# MAAV_Vehicle_13v1.net
KiCad netlist of a schematic drawn in EAGLE
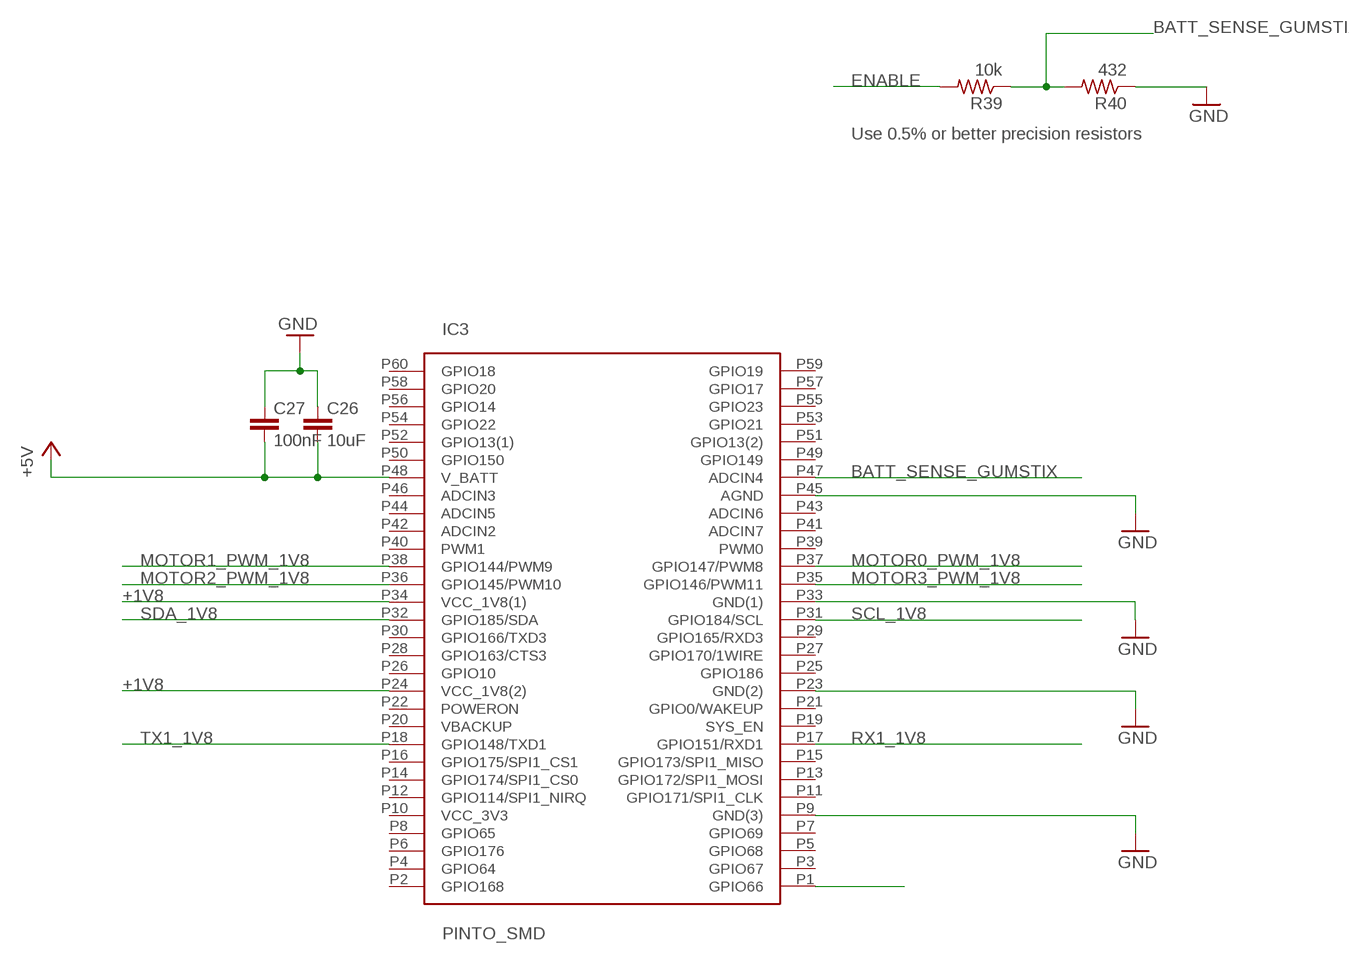
[diagram p0: schematic, sheet 1]
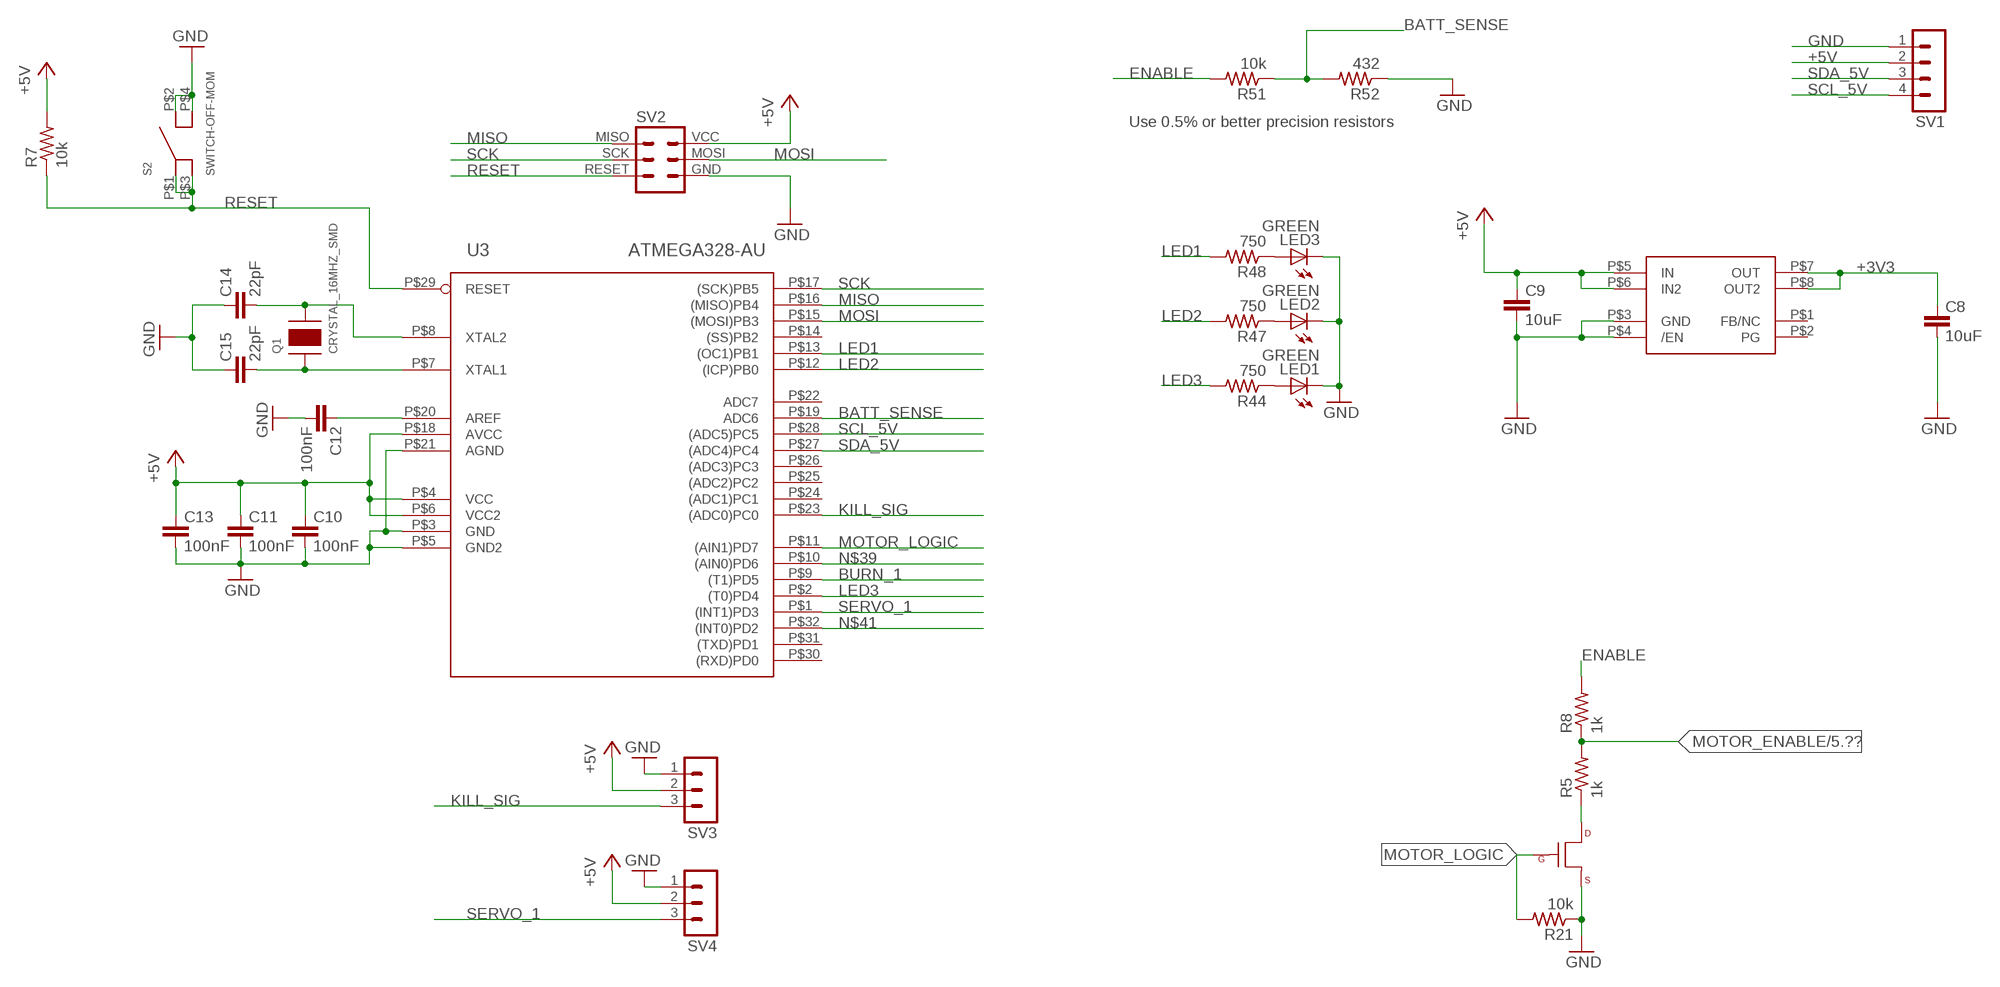
[diagram p1: schematic, sheet 2]
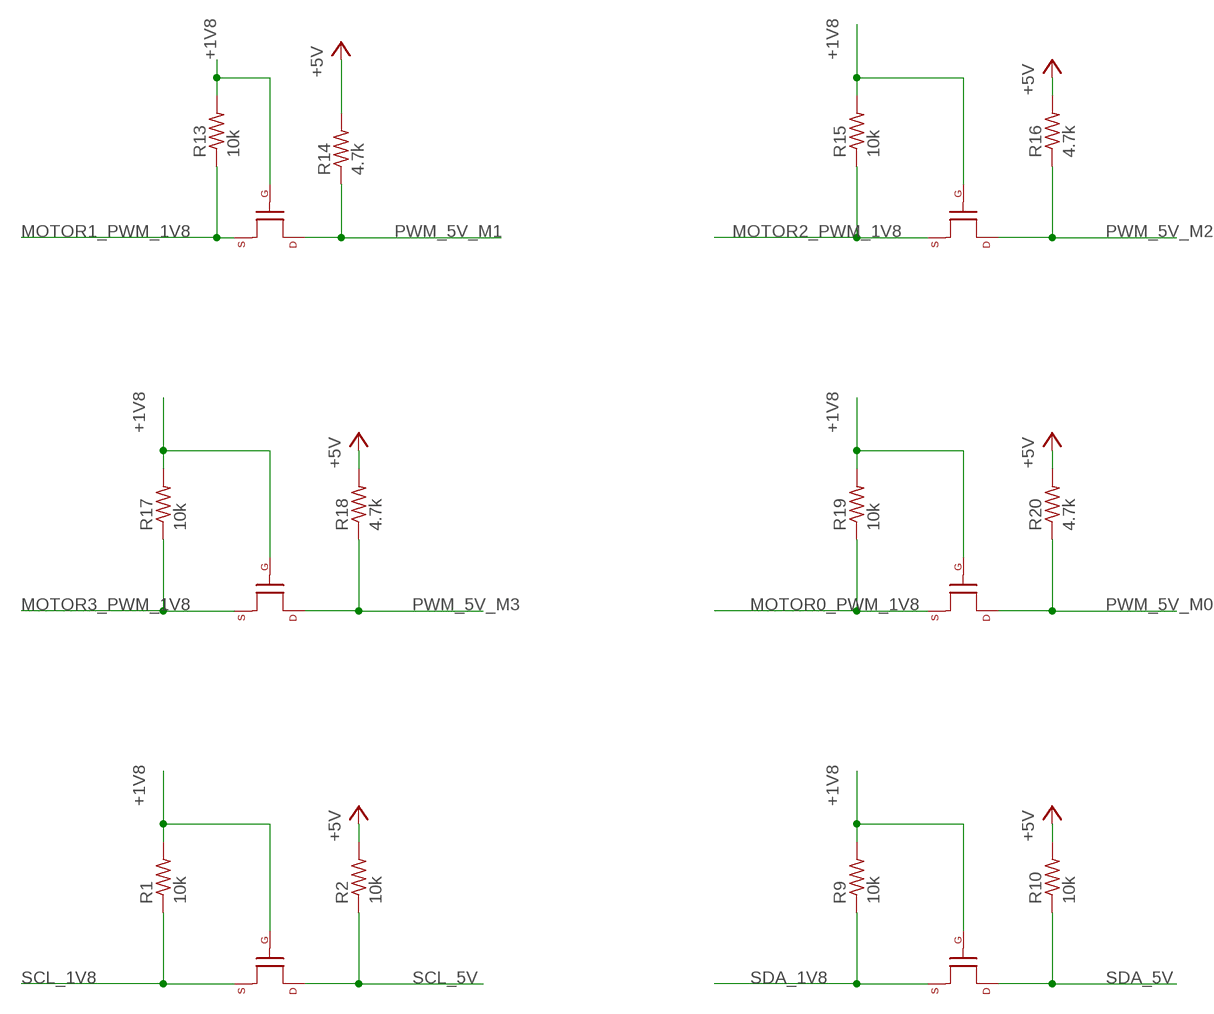
[diagram p2: schematic, sheet 3]
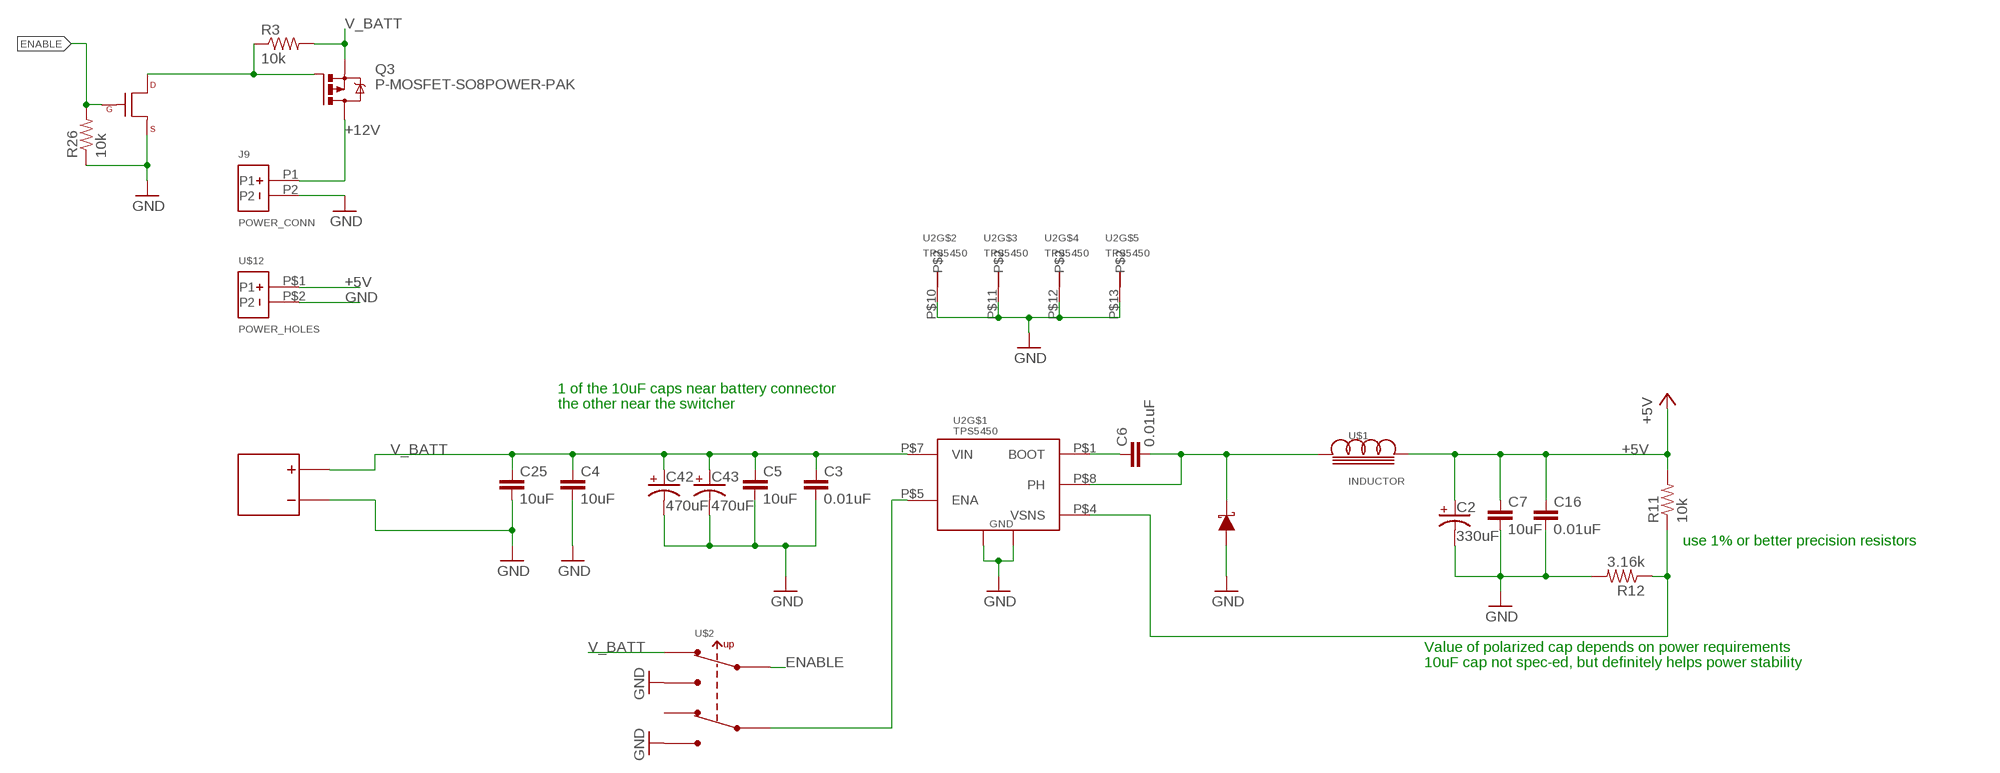
[diagram p3: schematic, sheet 4]
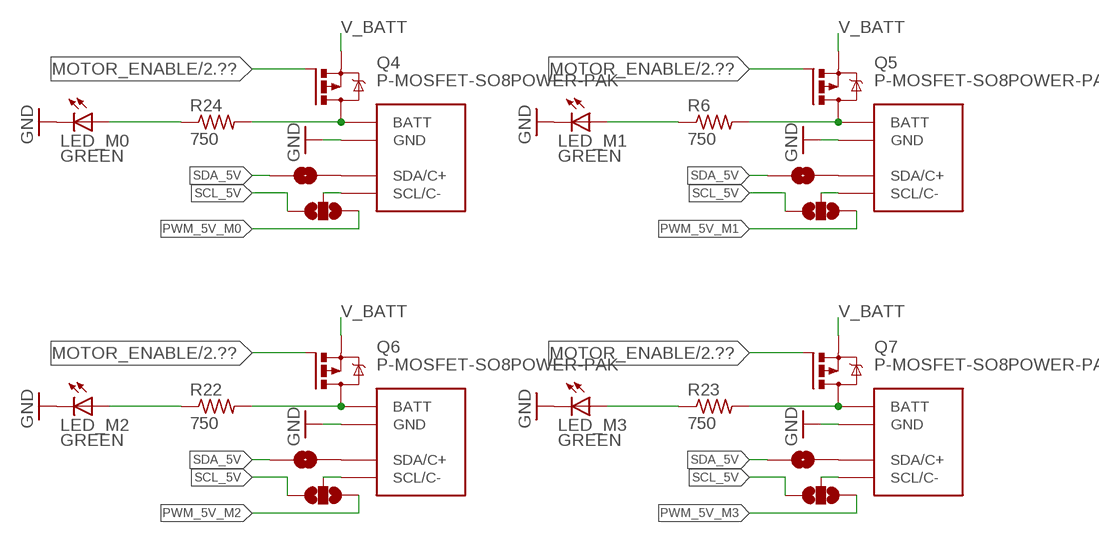
[diagram p4: schematic, sheet 5]
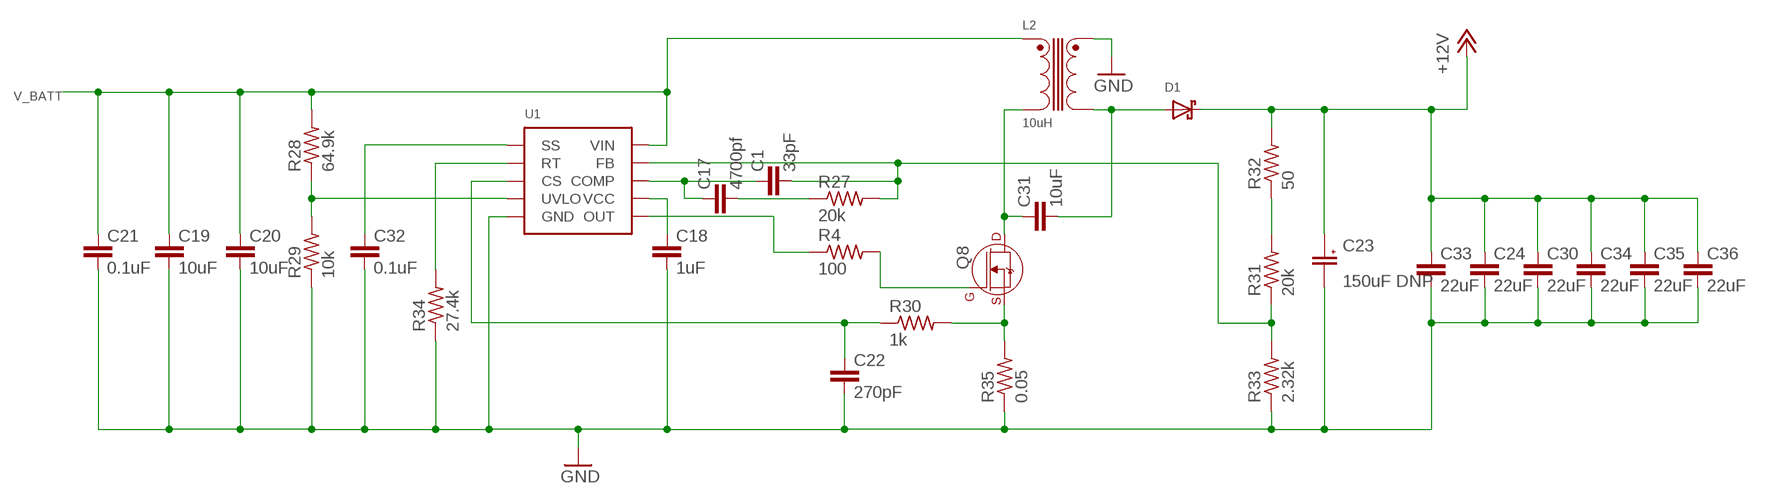
[diagram p5: schematic, sheet 6]
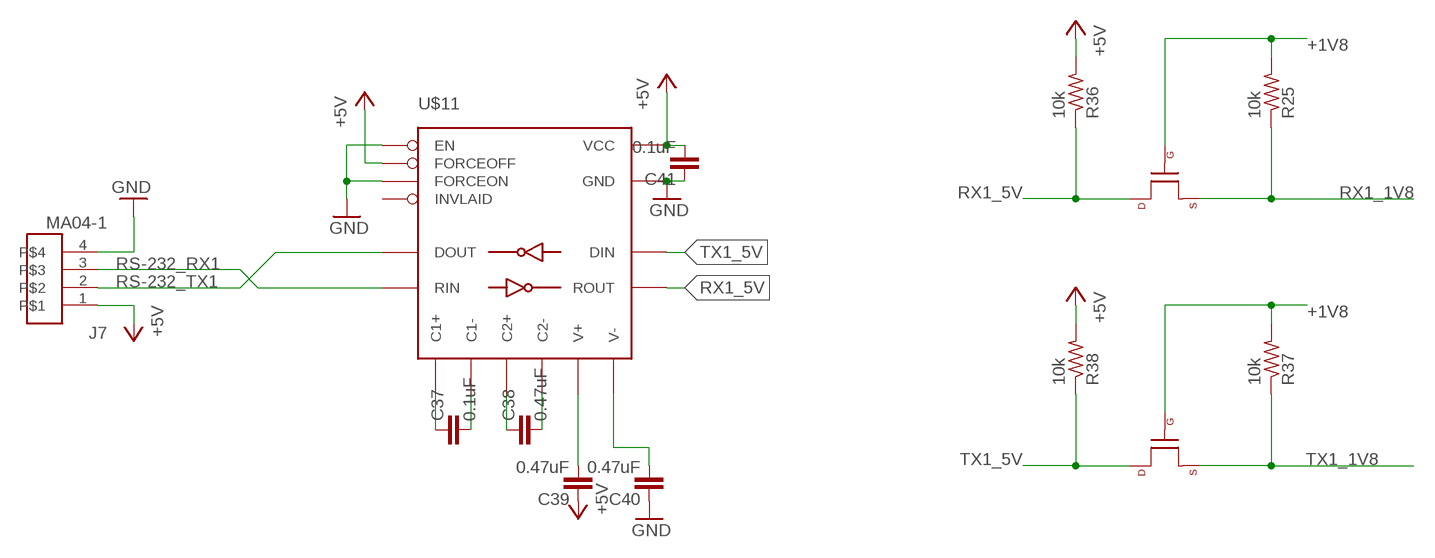
[diagram p6: schematic, sheet 7]
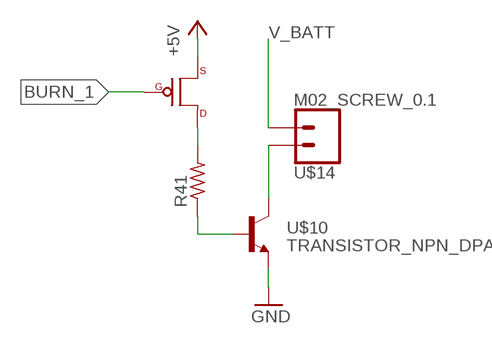
[diagram p7: schematic, sheet 8]

(export (version "E")
  (design (tool "Eeschema 10.0.6"))
  (components
    (comp (ref "C1")
      (value "33pF")
      (footprint "eagle-import:C0402")
      (fields (field (name "DIGIKEY#") "box"))
      (libsource (lib "eagle-import") (part "C-EUC0402"))
    )
    (comp (ref "C17")
      (value "4700pf")
      (footprint "eagle-import:C0402")
      (fields (field (name "DIGIKEY#") "box"))
      (libsource (lib "eagle-import") (part "C-EUC0402"))
    )
    (comp (ref "C18")
      (value "1uF")
      (footprint "eagle-import:C0603")
      (fields (field (name "DIGIKEY#") "587-2984-1-ND"))
      (libsource (lib "eagle-import") (part "C-EUC0603"))
    )
    (comp (ref "C19")
      (value "10uF")
      (footprint "eagle-import:C1206")
      (fields (field (name "DIGIKEY#") "587-2399-1-ND"))
      (libsource (lib "eagle-import") (part "C-EUC1206"))
    )
    (comp (ref "C20")
      (value "10uF")
      (footprint "eagle-import:C1206")
      (fields (field (name "DIGIKEY#") "587-2399-1-ND"))
      (libsource (lib "eagle-import") (part "C-EUC1206"))
    )
    (comp (ref "C21")
      (value "0.1uF")
      (footprint "eagle-import:C0603")
      (fields (field (name "DIGIKEY#") "1276-1000-1-ND"))
      (libsource (lib "eagle-import") (part "C-EUC0603"))
    )
    (comp (ref "C22")
      (value "270pF")
      (footprint "eagle-import:C0402")
      (fields (field (name "DIGIKEY#") "box"))
      (libsource (lib "eagle-import") (part "C-EUC0402"))
    )
    (comp (ref "C23")
      (value "150uF DNP")
      (footprint "eagle-import:C2917")
      (fields (field (name "PARTNUM") "399-4663-1-ND"))
      (libsource (lib "eagle-import") (part "T530X157M016ATE015"))
    )
    (comp (ref "C24")
      (value "22uF")
      (footprint "eagle-import:C1206")
      (fields (field (name "DIGIKEY#") "587-3246-1-ND"))
      (libsource (lib "eagle-import") (part "C-EUC1206"))
    )
    (comp (ref "C30")
      (value "22uF")
      (footprint "eagle-import:C1206")
      (fields (field (name "DIGIKEY#") "587-3246-1-ND"))
      (libsource (lib "eagle-import") (part "C-EUC1206"))
    )
    (comp (ref "C31")
      (value "10uF")
      (footprint "eagle-import:C1206")
      (fields (field (name "DIGIKEY#") "587-2399-1-ND"))
      (libsource (lib "eagle-import") (part "C-EUC1206"))
    )
    (comp (ref "C32")
      (value "0.1uF")
      (footprint "eagle-import:C0402")
      (fields (field (name "DIGIKEY#") "box"))
      (libsource (lib "eagle-import") (part "C-EUC0402"))
    )
    (comp (ref "C33")
      (value "22uF")
      (footprint "eagle-import:C1206")
      (fields (field (name "DIGIKEY#") "587-3246-1-ND"))
      (libsource (lib "eagle-import") (part "C-EUC1206"))
    )
    (comp (ref "C34")
      (value "22uF")
      (footprint "eagle-import:C1206")
      (fields (field (name "DIGIKEY#") "587-3246-1-ND"))
      (libsource (lib "eagle-import") (part "C-EUC1206"))
    )
    (comp (ref "C35")
      (value "22uF")
      (footprint "eagle-import:C1206")
      (fields (field (name "DIGIKEY#") "587-3246-1-ND"))
      (libsource (lib "eagle-import") (part "C-EUC1206"))
    )
    (comp (ref "C36")
      (value "22uF")
      (footprint "eagle-import:C1206")
      (fields (field (name "DIGIKEY#") "587-3246-1-ND"))
      (libsource (lib "eagle-import") (part "C-EUC1206"))
    )
    (comp (ref "D1")
      (value "PDS760")
      (footprint "eagle-import:PDS760")
      (libsource (lib "eagle-import") (part "PDS760"))
    )
    (comp (ref "L2")
      (value "10uH")
      (footprint "eagle-import:DRQ125")
      (fields (field (name "PARTNUM") "513-1289-1-ND"))
      (libsource (lib "eagle-import") (part "DRQ125"))
    )
    (comp (ref "Q8")
      (value "STL60N3LLH5")
      (footprint "eagle-import:POWERFLAT-8")
      (fields (field (name "PARTNUM") "497-11094-1-ND"))
      (libsource (lib "eagle-import") (part "STL60N3LLH5"))
    )
    (comp (ref "R4")
      (value "100")
      (footprint "eagle-import:R0402")
      (libsource (lib "eagle-import") (part "R-USR0402"))
    )
    (comp (ref "R27")
      (value "20k")
      (footprint "eagle-import:R0402")
      (libsource (lib "eagle-import") (part "R-USR0402"))
    )
    (comp (ref "R28")
      (value "64.9k")
      (footprint "eagle-import:R0402")
      (fields (field (name "DIGIKEY#") "P64.9KDCCT-ND"))
      (libsource (lib "eagle-import") (part "R-USR0402"))
    )
    (comp (ref "R29")
      (value "10k")
      (footprint "eagle-import:R0402")
      (fields (field (name "DIGIKEY#") "box"))
      (libsource (lib "eagle-import") (part "R-USR0402"))
    )
    (comp (ref "R30")
      (value "1k")
      (footprint "eagle-import:R0402")
      (fields (field (name "DIGIKEY#") "box"))
      (libsource (lib "eagle-import") (part "R-USR0402"))
    )
    (comp (ref "R31")
      (value "20k")
      (footprint "eagle-import:R0402")
      (fields (field (name "DIGIKEY#") "box"))
      (libsource (lib "eagle-import") (part "R-USR0402"))
    )
    (comp (ref "R32")
      (value "50")
      (footprint "eagle-import:R0402")
      (fields (field (name "DIGIKEY#") "box"))
      (libsource (lib "eagle-import") (part "R-USR0402"))
    )
    (comp (ref "R33")
      (value "2.32k")
      (footprint "eagle-import:R0402")
      (fields (field (name "DIGIKEY#") "P2.32KDCCT-ND"))
      (libsource (lib "eagle-import") (part "R-USR0402"))
    )
    (comp (ref "R34")
      (value "27.4k")
      (footprint "eagle-import:R0402")
      (fields (field (name "DIGIKEY#") "box"))
      (libsource (lib "eagle-import") (part "R-USR0402"))
    )
    (comp (ref "R35")
      (value "0.05")
      (footprint "eagle-import:R2512")
      (libsource (lib "eagle-import") (part "R-US_R2512"))
    )
    (comp (ref "U1")
      (value "LM5022")
      (footprint "eagle-import:MSOP-10")
      (fields (field (name "PARTNUM") "LM5022MM/NOPBCT-ND"))
      (libsource (lib "eagle-import") (part "LM5022"))
    )
    (comp (ref "C37")
      (value "0.1uF")
      (footprint "eagle-import:C0603")
      (fields (field (name "DIGIKEY#") "490-1524-1-ND"))
      (libsource (lib "eagle-import") (part "C-EUC0603"))
    )
    (comp (ref "C38")
      (value "0.47uF")
      (footprint "eagle-import:C0805")
      (fields (field (name "DIGIKEY#") "1276-2966-1-ND"))
      (libsource (lib "eagle-import") (part "C-EUC0805"))
    )
    (comp (ref "C39")
      (value "0.47uF")
      (footprint "eagle-import:C0805")
      (fields (field (name "DIGIKEY#") "1276-2966-1-ND"))
      (libsource (lib "eagle-import") (part "C-EUC0805"))
    )
    (comp (ref "C40")
      (value "0.47uF")
      (footprint "eagle-import:C0805")
      (fields (field (name "DIGIKEY#") "1276-2966-1-ND"))
      (libsource (lib "eagle-import") (part "C-EUC0805"))
    )
    (comp (ref "C41")
      (value "0.1uF")
      (footprint "eagle-import:C0603")
      (fields (field (name "DIGIKEY#") "490-1524-1-ND"))
      (libsource (lib "eagle-import") (part "C-EUC0603"))
    )
    (comp (ref "J7")
      (value "MA04-1")
      (footprint "eagle-import:MA-04-SMD")
      (libsource (lib "eagle-import") (part "MA04-1"))
    )
    (comp (ref "R25")
      (value "10k")
      (footprint "eagle-import:R0603")
      (fields (field (name "DIGIKEY#") "P10.0KHCT-ND"))
      (libsource (lib "eagle-import") (part "R-USR0603"))
    )
    (comp (ref "R36")
      (value "10k")
      (footprint "eagle-import:R0603")
      (fields (field (name "DIGIKEY#") "P10.0KHCT-ND"))
      (libsource (lib "eagle-import") (part "R-USR0603"))
    )
    (comp (ref "R37")
      (value "10k")
      (footprint "eagle-import:R0603")
      (fields (field (name "DIGIKEY#") "P10.0KHCT-ND"))
      (libsource (lib "eagle-import") (part "R-USR0603"))
    )
    (comp (ref "R38")
      (value "10k")
      (footprint "eagle-import:R0603")
      (fields (field (name "DIGIKEY#") "P10.0KHCT-ND"))
      (libsource (lib "eagle-import") (part "R-USR0603"))
    )
    (comp (ref "T1")
      (value "MOSFET-NCHANNELSMD")
      (footprint "eagle-import:SOT23-3")
      (fields (field (name "DIGIKEY#") "BSS138KCT-ND"))
      (libsource (lib "eagle-import") (part "MOSFET-NCHANNELSMD"))
    )
    (comp (ref "T2")
      (value "MOSFET-NCHANNELSMD")
      (footprint "eagle-import:SOT23-3")
      (fields (field (name "DIGIKEY#") "BSS138KCT-ND"))
      (libsource (lib "eagle-import") (part "MOSFET-NCHANNELSMD"))
    )
    (comp (ref "U$11")
      (value "MAX3221-RS232")
      (footprint "eagle-import:16-TSSOP")
      (fields (field (name "DIGIKEY#") "296-19825-1-ND"))
      (libsource (lib "eagle-import") (part "MAX3221-RS232"))
    )
    (comp (ref "R1")
      (value "10k")
      (footprint "eagle-import:R0603")
      (fields (field (name "DIGIKEY#") "P10.0KHCT-ND"))
      (libsource (lib "eagle-import") (part "R-USR0603"))
    )
    (comp (ref "R2")
      (value "10k")
      (footprint "eagle-import:R0603")
      (fields (field (name "DIGIKEY#") "P10.0KHCT-ND"))
      (libsource (lib "eagle-import") (part "R-USR0603"))
    )
    (comp (ref "R9")
      (value "10k")
      (footprint "eagle-import:R0603")
      (fields (field (name "DIGIKEY#") "P10.0KHCT-ND"))
      (libsource (lib "eagle-import") (part "R-USR0603"))
    )
    (comp (ref "R10")
      (value "10k")
      (footprint "eagle-import:R0603")
      (fields (field (name "DIGIKEY#") "P10.0KHCT-ND"))
      (libsource (lib "eagle-import") (part "R-USR0603"))
    )
    (comp (ref "R13")
      (value "10k")
      (footprint "eagle-import:R0603")
      (fields (field (name "DIGIKEY#") "P10.0KHCT-ND"))
      (libsource (lib "eagle-import") (part "R-USR0603"))
    )
    (comp (ref "R14")
      (value "4.7k")
      (footprint "eagle-import:R0603")
      (fields (field (name "DIGIKEY#") "P4.70KHCT-ND"))
      (libsource (lib "eagle-import") (part "R-USR0603"))
    )
    (comp (ref "R15")
      (value "10k")
      (footprint "eagle-import:R0603")
      (fields (field (name "DIGIKEY#") "P10.0KHCT-ND"))
      (libsource (lib "eagle-import") (part "R-USR0603"))
    )
    (comp (ref "R16")
      (value "4.7k")
      (footprint "eagle-import:R0603")
      (fields (field (name "DIGIKEY#") "P4.70KHCT-ND"))
      (libsource (lib "eagle-import") (part "R-USR0603"))
    )
    (comp (ref "R17")
      (value "10k")
      (footprint "eagle-import:R0603")
      (fields (field (name "DIGIKEY#") "P10.0KHCT-ND"))
      (libsource (lib "eagle-import") (part "R-USR0603"))
    )
    (comp (ref "R18")
      (value "4.7k")
      (footprint "eagle-import:R0603")
      (fields (field (name "DIGIKEY#") "P4.70KHCT-ND"))
      (libsource (lib "eagle-import") (part "R-USR0603"))
    )
    (comp (ref "R19")
      (value "10k")
      (footprint "eagle-import:R0603")
      (fields (field (name "DIGIKEY#") "P10.0KHCT-ND"))
      (libsource (lib "eagle-import") (part "R-USR0603"))
    )
    (comp (ref "R20")
      (value "4.7k")
      (footprint "eagle-import:R0603")
      (fields (field (name "DIGIKEY#") "P4.70KHCT-ND"))
      (libsource (lib "eagle-import") (part "R-USR0603"))
    )
    (comp (ref "T3")
      (value "MOSFET-NCHANNELSMD")
      (footprint "eagle-import:SOT23-3")
      (fields (field (name "DIGIKEY#") "BSS138KCT-ND"))
      (libsource (lib "eagle-import") (part "MOSFET-NCHANNELSMD"))
    )
    (comp (ref "T4")
      (value "MOSFET-NCHANNELSMD")
      (footprint "eagle-import:SOT23-3")
      (fields (field (name "DIGIKEY#") "BSS138KCT-ND"))
      (libsource (lib "eagle-import") (part "MOSFET-NCHANNELSMD"))
    )
    (comp (ref "T7")
      (value "MOSFET-NCHANNELSMD")
      (footprint "eagle-import:SOT23-3")
      (fields (field (name "DIGIKEY#") "BSS138KCT-ND"))
      (libsource (lib "eagle-import") (part "MOSFET-NCHANNELSMD"))
    )
    (comp (ref "T8")
      (value "MOSFET-NCHANNELSMD")
      (footprint "eagle-import:SOT23-3")
      (fields (field (name "DIGIKEY#") "BSS138KCT-ND"))
      (libsource (lib "eagle-import") (part "MOSFET-NCHANNELSMD"))
    )
    (comp (ref "T9")
      (value "MOSFET-NCHANNELSMD")
      (footprint "eagle-import:SOT23-3")
      (fields (field (name "DIGIKEY#") "BSS138KCT-ND"))
      (libsource (lib "eagle-import") (part "MOSFET-NCHANNELSMD"))
    )
    (comp (ref "T10")
      (value "MOSFET-NCHANNELSMD")
      (footprint "eagle-import:SOT23-3")
      (fields (field (name "DIGIKEY#") "BSS138KCT-ND"))
      (libsource (lib "eagle-import") (part "MOSFET-NCHANNELSMD"))
    )
    (comp (ref "LED_M0")
      (value "GREEN")
      (footprint "eagle-import:CHIPLED_0805")
      (libsource (lib "eagle-import") (part "LEDCHIPLED_0805"))
    )
    (comp (ref "LED_M1")
      (value "GREEN")
      (footprint "eagle-import:CHIPLED_0805")
      (libsource (lib "eagle-import") (part "LEDCHIPLED_0805"))
    )
    (comp (ref "LED_M2")
      (value "GREEN")
      (footprint "eagle-import:CHIPLED_0805")
      (libsource (lib "eagle-import") (part "LEDCHIPLED_0805"))
    )
    (comp (ref "LED_M3")
      (value "GREEN")
      (footprint "eagle-import:CHIPLED_0805")
      (libsource (lib "eagle-import") (part "LEDCHIPLED_0805"))
    )
    (comp (ref "Q4")
      (value "P-MOSFET-SO8POWER-PAK")
      (footprint "eagle-import:SO-8_POWER-PAK")
      (libsource (lib "eagle-import") (part "P-MOSFET-SO8POWER-PAK"))
    )
    (comp (ref "Q5")
      (value "P-MOSFET-SO8POWER-PAK")
      (footprint "eagle-import:SO-8_POWER-PAK")
      (libsource (lib "eagle-import") (part "P-MOSFET-SO8POWER-PAK"))
    )
    (comp (ref "Q6")
      (value "P-MOSFET-SO8POWER-PAK")
      (footprint "eagle-import:SO-8_POWER-PAK")
      (libsource (lib "eagle-import") (part "P-MOSFET-SO8POWER-PAK"))
    )
    (comp (ref "Q7")
      (value "P-MOSFET-SO8POWER-PAK")
      (footprint "eagle-import:SO-8_POWER-PAK")
      (libsource (lib "eagle-import") (part "P-MOSFET-SO8POWER-PAK"))
    )
    (comp (ref "R6")
      (value "750")
      (footprint "eagle-import:R0805")
      (fields (field (name "DIGIKEY#") "P750CCT-ND"))
      (libsource (lib "eagle-import") (part "R-USR0805"))
    )
    (comp (ref "R22")
      (value "750")
      (footprint "eagle-import:R0805")
      (fields (field (name "DIGIKEY#") "P750CCT-ND"))
      (libsource (lib "eagle-import") (part "R-USR0805"))
    )
    (comp (ref "R23")
      (value "750")
      (footprint "eagle-import:R0805")
      (fields (field (name "DIGIKEY#") "P750CCT-ND"))
      (libsource (lib "eagle-import") (part "R-USR0805"))
    )
    (comp (ref "R24")
      (value "750")
      (footprint "eagle-import:R0805")
      (fields (field (name "DIGIKEY#") "P750CCT-ND"))
      (libsource (lib "eagle-import") (part "R-USR0805"))
    )
    (comp (ref "SJ1")
      (value "SOLDERJUMPERNO")
      (footprint "eagle-import:SJ_2S-NO")
      (libsource (lib "eagle-import") (part "SOLDERJUMPERNO"))
    )
    (comp (ref "SJ2")
      (value "SOLDERJUMPERNO")
      (footprint "eagle-import:SJ_2S-NO")
      (libsource (lib "eagle-import") (part "SOLDERJUMPERNO"))
    )
    (comp (ref "SJ3")
      (value "SOLDERJUMPER_2WAYS")
      (footprint "eagle-import:SJ_3")
      (libsource (lib "eagle-import") (part "SOLDERJUMPER_2WAYS"))
    )
    (comp (ref "SJ4")
      (value "SOLDERJUMPER_2WAYS")
      (footprint "eagle-import:SJ_3")
      (libsource (lib "eagle-import") (part "SOLDERJUMPER_2WAYS"))
    )
    (comp (ref "SJ5")
      (value "SOLDERJUMPERNO")
      (footprint "eagle-import:SJ_2S-NO")
      (libsource (lib "eagle-import") (part "SOLDERJUMPERNO"))
    )
    (comp (ref "SJ6")
      (value "SOLDERJUMPER_2WAYS")
      (footprint "eagle-import:SJ_3")
      (libsource (lib "eagle-import") (part "SOLDERJUMPER_2WAYS"))
    )
    (comp (ref "SJ7")
      (value "SOLDERJUMPERNO")
      (footprint "eagle-import:SJ_2S-NO")
      (libsource (lib "eagle-import") (part "SOLDERJUMPERNO"))
    )
    (comp (ref "SJ8")
      (value "SOLDERJUMPER_2WAYS")
      (footprint "eagle-import:SJ_3")
      (libsource (lib "eagle-import") (part "SOLDERJUMPER_2WAYS"))
    )
    (comp (ref "U$3")
      (value "ESC_CONN")
      (footprint "eagle-import:ESC_CONN")
      (libsource (lib "eagle-import") (part "ESC_CONN"))
    )
    (comp (ref "U$4")
      (value "ESC_CONN")
      (footprint "eagle-import:ESC_CONN")
      (libsource (lib "eagle-import") (part "ESC_CONN"))
    )
    (comp (ref "U$5")
      (value "ESC_CONN")
      (footprint "eagle-import:ESC_CONN")
      (libsource (lib "eagle-import") (part "ESC_CONN"))
    )
    (comp (ref "U$6")
      (value "ESC_CONN")
      (footprint "eagle-import:ESC_CONN")
      (libsource (lib "eagle-import") (part "ESC_CONN"))
    )
    (comp (ref "C2")
      (value "330uF")
      (footprint "eagle-import:C_2917_POL")
      (libsource (lib "eagle-import") (part "C-POL-TANT"))
    )
    (comp (ref "C3")
      (value "0.01uF")
      (footprint "eagle-import:C0603")
      (fields (field (name "DIGIKEY#") "490-1512-1-ND"))
      (libsource (lib "eagle-import") (part "C-EUC0603"))
    )
    (comp (ref "C4")
      (value "10uF")
      (footprint "eagle-import:C1206")
      (fields (field (name "DIGIKEY#") "587-2399-1-ND"))
      (libsource (lib "eagle-import") (part "C-EUC1206"))
    )
    (comp (ref "C5")
      (value "10uF")
      (footprint "eagle-import:C1206")
      (fields (field (name "DIGIKEY#") "587-2399-1-ND"))
      (libsource (lib "eagle-import") (part "C-EUC1206"))
    )
    (comp (ref "C6")
      (value "0.01uF")
      (footprint "eagle-import:C0603")
      (fields (field (name "DIGIKEY#") "490-1512-1-ND"))
      (libsource (lib "eagle-import") (part "C-EUC0603"))
    )
    (comp (ref "C7")
      (value "10uF")
      (footprint "eagle-import:C1206")
      (fields (field (name "DIGIKEY#") "587-2399-1-ND"))
      (libsource (lib "eagle-import") (part "C-EUC1206"))
    )
    (comp (ref "C16")
      (value "0.01uF")
      (footprint "eagle-import:C0603")
      (fields (field (name "DIGIKEY#") "490-1512-1-ND"))
      (libsource (lib "eagle-import") (part "C-EUC0603"))
    )
    (comp (ref "C25")
      (value "10uF")
      (footprint "eagle-import:C1206")
      (fields (field (name "DIGIKEY#") "587-2399-1-ND"))
      (libsource (lib "eagle-import") (part "C-EUC1206"))
    )
    (comp (ref "C42")
      (value "470uF")
      (footprint "eagle-import:EH22-9")
      (fields (field (name "DIGIEKY#") "P14440-ND"))
      (libsource (lib "eagle-import") (part "C-POL-AL-8-22"))
    )
    (comp (ref "C43")
      (value "470uF")
      (footprint "eagle-import:EH22-9")
      (fields (field (name "DIGIEKY#") "P14440-ND"))
      (libsource (lib "eagle-import") (part "C-POL-AL-8-22"))
    )
    (comp (ref "J9")
      (value "POWER_CONN")
      (footprint "eagle-import:POWER_CONN")
      (libsource (lib "eagle-import") (part "POWER_CONN"))
    )
    (comp (ref "Q2")
      (value "MOSFET-NCHANNELSMD")
      (footprint "eagle-import:SOT23-3")
      (fields (field (name "DIGIKEY#") "BSS84CT-ND"))
      (libsource (lib "eagle-import") (part "MOSFET-NCHANNELSMD"))
    )
    (comp (ref "Q3")
      (value "P-MOSFET-SO8POWER-PAK")
      (footprint "eagle-import:SO-8_POWER-PAK")
      (fields (field (name "DIGIKEY#") "SI7135DP-T1-GE3CT-ND"))
      (libsource (lib "eagle-import") (part "P-MOSFET-SO8POWER-PAK"))
    )
    (comp (ref "R3")
      (value "10k")
      (footprint "eagle-import:R0603")
      (fields (field (name "DIGIKEY#") "P10.0KHCT-ND"))
      (libsource (lib "eagle-import") (part "R-USR0603"))
    )
    (comp (ref "R11")
      (value "10k")
      (footprint "eagle-import:R0603")
      (fields (field (name "DIGIKEY#") "P10KDBCT-ND"))
      (libsource (lib "eagle-import") (part "R-USR0603"))
    )
    (comp (ref "R12")
      (value "3.16k")
      (footprint "eagle-import:R0603")
      (fields (field (name "DIGIKEY#") "311-3.16KDCT-ND"))
      (libsource (lib "eagle-import") (part "R-USR0603"))
    )
    (comp (ref "R26")
      (value "10k")
      (footprint "eagle-import:R0603")
      (fields (field (name "DIGIKEY#") "P10.0KHCT-ND"))
      (libsource (lib "eagle-import") (part "R-USR0603"))
    )
    (comp (ref "U$1")
      (value "INDUCTOR")
      (footprint "eagle-import:CDRH127")
      (libsource (lib "eagle-import") (part "INDUCTOR"))
    )
    (comp (ref "U$2")
      (value "SWITCH_DPDT")
      (footprint "eagle-import:SWITCH_VERT_DPDT")
      (libsource (lib "eagle-import") (part "SWITCH_DPDT"))
    )
    (comp (ref "U$9")
      (value "DIODE-SCHOTTKYBIG")
      (footprint "eagle-import:DO-214AB,SMC")
      (libsource (lib "eagle-import") (part "DIODE-SCHOTTKYBIG"))
    )
    (comp (ref "U$12")
      (value "POWER_HOLES")
      (footprint "eagle-import:POWER_HOLES")
      (libsource (lib "eagle-import") (part "POWER_HOLES"))
    )
    (comp (ref "U$13")
      (value "BATTERY50A")
      (footprint "eagle-import:LIPO_POWER_50A")
      (libsource (lib "eagle-import") (part "BATTERY50A"))
    )
    (comp (ref "U2")
      (value "TPS5450")
      (footprint "eagle-import:TPS5450")
      (fields (field (name "DIGIKEY#") "296-23750-1-ND"))
      (libsource (lib "eagle-import") (part "TPS5450"))
    )
    (comp (ref "C8")
      (value "10uF")
      (footprint "eagle-import:C1206")
      (fields (field (name "DIGIKEY#") "587-2399-1-ND"))
      (libsource (lib "eagle-import") (part "C-EUC1206"))
    )
    (comp (ref "C9")
      (value "10uF")
      (footprint "eagle-import:C1206")
      (fields (field (name "DIGIKEY#") "587-2399-1-ND"))
      (libsource (lib "eagle-import") (part "C-EUC1206"))
    )
    (comp (ref "C10")
      (value "100nF")
      (footprint "eagle-import:C0603")
      (fields (field (name "DIGIKEY#") "1276-1000-1-ND"))
      (libsource (lib "eagle-import") (part "C-EUC0603"))
    )
    (comp (ref "C11")
      (value "100nF")
      (footprint "eagle-import:C0603")
      (fields (field (name "DIGIKEY#") "1276-1000-1-ND"))
      (libsource (lib "eagle-import") (part "C-EUC0603"))
    )
    (comp (ref "C12")
      (value "100nF")
      (footprint "eagle-import:C0603")
      (fields (field (name "DIGIKEY#") "1276-1000-1-ND"))
      (libsource (lib "eagle-import") (part "C-EUC0603"))
    )
    (comp (ref "C13")
      (value "100nF")
      (footprint "eagle-import:C0603")
      (fields (field (name "DIGIKEY#") "1276-1000-1-ND"))
      (libsource (lib "eagle-import") (part "C-EUC0603"))
    )
    (comp (ref "C14")
      (value "22pF")
      (footprint "eagle-import:C0603")
      (fields (field (name "DIGIKEY#") "478-6200-1-ND"))
      (libsource (lib "eagle-import") (part "C-EUC0603"))
    )
    (comp (ref "C15")
      (value "22pF")
      (footprint "eagle-import:C0603")
      (fields (field (name "DIGIKEY#") "478-6200-1-ND"))
      (libsource (lib "eagle-import") (part "C-EUC0603"))
    )
    (comp (ref "LED1")
      (value "GREEN")
      (footprint "eagle-import:CHIPLED_0603")
      (libsource (lib "eagle-import") (part "LEDCHIPLED_0603"))
    )
    (comp (ref "LED2")
      (value "GREEN")
      (footprint "eagle-import:CHIPLED_0603")
      (libsource (lib "eagle-import") (part "LEDCHIPLED_0603"))
    )
    (comp (ref "LED3")
      (value "GREEN")
      (footprint "eagle-import:CHIPLED_0603")
      (libsource (lib "eagle-import") (part "LEDCHIPLED_0603"))
    )
    (comp (ref "Q1")
      (value "CRYSTAL_16MHZ_SMD")
      (footprint "eagle-import:4-SMD_DFN")
      (libsource (lib "eagle-import") (part "CRYSTAL_16MHZ_SMD"))
    )
    (comp (ref "R5")
      (value "1k")
      (footprint "eagle-import:R0603")
      (fields (field (name "DIGIKEY#") "P1.00KHCT-ND"))
      (libsource (lib "eagle-import") (part "R-USR0603"))
    )
    (comp (ref "R7")
      (value "10k")
      (footprint "eagle-import:R0603")
      (fields (field (name "DIGIKEY#") "P10.0KHCT-ND"))
      (libsource (lib "eagle-import") (part "R-USR0603"))
    )
    (comp (ref "R8")
      (value "1k")
      (footprint "eagle-import:R0603")
      (fields (field (name "DIGIKEY#") "P1.00KHCT-ND"))
      (libsource (lib "eagle-import") (part "R-USR0603"))
    )
    (comp (ref "R21")
      (value "10k")
      (footprint "eagle-import:R0603")
      (fields (field (name "DIGIKEY#") "P10.0KHCT-ND"))
      (libsource (lib "eagle-import") (part "R-USR0603"))
    )
    (comp (ref "R44")
      (value "750")
      (footprint "eagle-import:R0805")
      (fields (field (name "DIGIKEY#") "P750CCT-ND"))
      (libsource (lib "eagle-import") (part "R-USR0805"))
    )
    (comp (ref "R47")
      (value "750")
      (footprint "eagle-import:R0805")
      (fields (field (name "DIGIKEY#") "P750CCT-ND"))
      (libsource (lib "eagle-import") (part "R-USR0805"))
    )
    (comp (ref "R48")
      (value "750")
      (footprint "eagle-import:R0805")
      (fields (field (name "DIGIKEY#") "P750CCT-ND"))
      (libsource (lib "eagle-import") (part "R-USR0805"))
    )
    (comp (ref "R51")
      (value "10k")
      (footprint "eagle-import:R0603")
      (fields (field (name "DIGIKEY#") "P10KDBCT-ND"))
      (libsource (lib "eagle-import") (part "R-USR0603"))
    )
    (comp (ref "R52")
      (value "432")
      (footprint "eagle-import:R0603")
      (fields (field (name "DIGIKEY#") "P432DBCT-ND"))
      (libsource (lib "eagle-import") (part "R-USR0603"))
    )
    (comp (ref "S2")
      (value "SWITCH-OFF-MOM")
      (footprint "eagle-import:SWITCH-OFF-MOM")
      (libsource (lib "eagle-import") (part "SWITCH-OFF-MOM"))
    )
    (comp (ref "SV1")
      (value "MA04-1")
      (footprint "eagle-import:MA04-1")
      (libsource (lib "eagle-import") (part "con-lstb_MA04-1"))
    )
    (comp (ref "SV2")
      (value "AVRISP-63X2_SMD")
      (footprint "eagle-import:AVRISP-6-SMD")
      (libsource (lib "eagle-import") (part "AVRISP-63X2_SMD"))
    )
    (comp (ref "SV3")
      (value "MA03-1")
      (footprint "eagle-import:MA03-1")
      (libsource (lib "eagle-import") (part "MA03-1"))
    )
    (comp (ref "SV4")
      (value "MA03-1")
      (footprint "eagle-import:MA03-1")
      (libsource (lib "eagle-import") (part "MA03-1"))
    )
    (comp (ref "T11")
      (value "MOSFET-NCHANNELSMD")
      (footprint "eagle-import:SOT23-3")
      (fields (field (name "DIGIKEY#") "BSS138KCT-ND"))
      (libsource (lib "eagle-import") (part "MOSFET-NCHANNELSMD"))
    )
    (comp (ref "U3")
      (value "ATMEGA328-AU")
      (footprint "eagle-import:32-TQFP")
      (libsource (lib "eagle-import") (part "ATMEGA328-AU"))
    )
    (comp (ref "U4")
      (value "REG_3V_8SOIC")
      (footprint "eagle-import:8-SOIC")
      (libsource (lib "eagle-import") (part "REG_3V_8SOIC"))
    )
    (comp (ref "R41")
      (value "R-USR1206")
      (footprint "eagle-import:R1206")
      (libsource (lib "eagle-import") (part "R-USR1206"))
    )
    (comp (ref "U$10")
      (value "TRANSISTOR_NPN_DPAK")
      (footprint "eagle-import:DPAK")
      (fields (field (name "DIGIKEY#") "497-12849-1-ND"))
      (libsource (lib "eagle-import") (part "TRANSISTOR_NPN_DPAK"))
    )
    (comp (ref "U$14")
      (value "M02_SCREW_0.1")
      (footprint "eagle-import:SCREW_TERM_2POS")
      (libsource (lib "eagle-import") (part "M02_SCREW_0.1"))
    )
    (comp (ref "U$15")
      (value "MOSFET-PCHANNEL_SOT23-3")
      (footprint "eagle-import:SOT23-3")
      (libsource (lib "eagle-import") (part "MOSFET-PCHANNEL_SOT23-3"))
    )
    (comp (ref "C26")
      (value "10uF")
      (footprint "eagle-import:C1206")
      (fields (field (name "DIGIKEY#") "587-2399-1-ND"))
      (libsource (lib "eagle-import") (part "C-EUC1206"))
    )
    (comp (ref "C27")
      (value "100nF")
      (footprint "eagle-import:C0603")
      (fields (field (name "DIGIKEY#") "1276-1000-1-ND"))
      (libsource (lib "eagle-import") (part "C-EUC0603"))
    )
    (comp (ref "IC3")
      (value "PINTO_SMD")
      (footprint "eagle-import:PINTO_SMD")
      (libsource (lib "eagle-import") (part "PINTO_SMD"))
    )
    (comp (ref "R39")
      (value "10k")
      (footprint "eagle-import:R0603")
      (fields (field (name "DIGIKEY#") "P10KDBCT-ND"))
      (libsource (lib "eagle-import") (part "R-USR0603"))
    )
    (comp (ref "R40")
      (value "432")
      (footprint "eagle-import:R0603")
      (fields (field (name "DIGIKEY#") "P432DBCT-ND"))
      (libsource (lib "eagle-import") (part "R-USR0603"))
    )
  )
  (nets
    (net (code "1") (name "+1V8") (class "Default")
      (node (ref "IC3") (pin "P24") (pinfunction "VCC_1V8(2)_P24") (pintype "bidirectional"))
      (node (ref "IC3") (pin "P34") (pinfunction "VCC_1V8(1)_P34") (pintype "bidirectional"))
      (node (ref "R1") (pin "2") (pinfunction "2_2") (pintype "passive"))
      (node (ref "R13") (pin "2") (pinfunction "2_2") (pintype "passive"))
      (node (ref "R15") (pin "2") (pinfunction "2_2") (pintype "passive"))
      (node (ref "R17") (pin "2") (pinfunction "2_2") (pintype "passive"))
      (node (ref "R19") (pin "2") (pinfunction "2_2") (pintype "passive"))
      (node (ref "R25") (pin "2") (pinfunction "2_2") (pintype "passive"))
      (node (ref "R37") (pin "2") (pinfunction "2_2") (pintype "passive"))
      (node (ref "R9") (pin "2") (pinfunction "2_2") (pintype "passive"))
      (node (ref "T1") (pin "1") (pinfunction "G_1") (pintype "passive"))
      (node (ref "T10") (pin "1") (pinfunction "G_1") (pintype "passive"))
      (node (ref "T2") (pin "1") (pinfunction "G_1") (pintype "passive"))
      (node (ref "T3") (pin "1") (pinfunction "G_1") (pintype "passive"))
      (node (ref "T4") (pin "1") (pinfunction "G_1") (pintype "passive"))
      (node (ref "T7") (pin "1") (pinfunction "G_1") (pintype "passive"))
      (node (ref "T8") (pin "1") (pinfunction "G_1") (pintype "passive"))
      (node (ref "T9") (pin "1") (pinfunction "G_1") (pintype "passive"))
    )
    (net (code "2") (name "+3V3") (class "Default")
      (node (ref "C8") (pin "1") (pinfunction "1_1") (pintype "passive"))
      (node (ref "U4") (pin "P$7") (pinfunction "OUT_P$7") (pintype "bidirectional"))
      (node (ref "U4") (pin "P$8") (pinfunction "OUT2_P$8") (pintype "bidirectional"))
    )
    (net (code "3") (name "+5V") (class "Default")
      (node (ref "C10") (pin "1") (pinfunction "1_1") (pintype "passive"))
      (node (ref "C11") (pin "1") (pinfunction "1_1") (pintype "passive"))
      (node (ref "C13") (pin "1") (pinfunction "1_1") (pintype "passive"))
      (node (ref "C16") (pin "1") (pinfunction "1_1") (pintype "passive"))
      (node (ref "C2") (pin "A") (pinfunction "ANODE_A") (pintype "bidirectional"))
      (node (ref "C26") (pin "2") (pinfunction "2_2") (pintype "passive"))
      (node (ref "C27") (pin "2") (pinfunction "2_2") (pintype "passive"))
      (node (ref "C39") (pin "1") (pinfunction "1_1") (pintype "passive"))
      (node (ref "C41") (pin "2") (pinfunction "2_2") (pintype "passive"))
      (node (ref "C7") (pin "1") (pinfunction "1_1") (pintype "passive"))
      (node (ref "C9") (pin "1") (pinfunction "1_1") (pintype "passive"))
      (node (ref "IC3") (pin "P48") (pinfunction "V_BATT_P48") (pintype "bidirectional"))
      (node (ref "J7") (pin "1") (pinfunction "P$1_1") (pintype "bidirectional"))
      (node (ref "R10") (pin "2") (pinfunction "2_2") (pintype "passive"))
      (node (ref "R11") (pin "2") (pinfunction "2_2") (pintype "passive"))
      (node (ref "R14") (pin "2") (pinfunction "2_2") (pintype "passive"))
      (node (ref "R16") (pin "2") (pinfunction "2_2") (pintype "passive"))
      (node (ref "R18") (pin "2") (pinfunction "2_2") (pintype "passive"))
      (node (ref "R2") (pin "2") (pinfunction "2_2") (pintype "passive"))
      (node (ref "R20") (pin "2") (pinfunction "2_2") (pintype "passive"))
      (node (ref "R36") (pin "2") (pinfunction "2_2") (pintype "passive"))
      (node (ref "R38") (pin "2") (pinfunction "2_2") (pintype "passive"))
      (node (ref "R7") (pin "2") (pinfunction "2_2") (pintype "passive"))
      (node (ref "SV1") (pin "2") (pinfunction "2_2") (pintype "passive"))
      (node (ref "SV2") (pin "VCC") (pinfunction "VCC_VCC") (pintype "passive"))
      (node (ref "SV3") (pin "2") (pinfunction "2_2") (pintype "passive"))
      (node (ref "SV4") (pin "2") (pinfunction "2_2") (pintype "passive"))
      (node (ref "U$1") (pin "P2") (pinfunction "2_P2") (pintype "bidirectional"))
      (node (ref "U$11") (pin "P$15") (pinfunction "VCC_P$15") (pintype "power_in"))
      (node (ref "U$11") (pin "P$16") (pinfunction "FORCEOFF_P$16") (pintype "input"))
      (node (ref "U$12") (pin "P$1") (pinfunction "P1_P$1") (pintype "bidirectional"))
      (node (ref "U$15") (pin "3") (pinfunction "D_3") (pintype "passive"))
      (node (ref "U3") (pin "P$18") (pinfunction "AVCC_P$18") (pintype "bidirectional"))
      (node (ref "U3") (pin "P$4") (pinfunction "VCC_P$4") (pintype "bidirectional"))
      (node (ref "U3") (pin "P$6") (pinfunction "VCC2_P$6") (pintype "bidirectional"))
      (node (ref "U4") (pin "P$5") (pinfunction "IN_P$5") (pintype "bidirectional"))
      (node (ref "U4") (pin "P$6") (pinfunction "IN2_P$6") (pintype "bidirectional"))
    )
    (net (code "4") (name "+12V") (class "Default")
      (node (ref "C23") (pin "+") (pinfunction "+_+") (pintype "bidirectional"))
      (node (ref "C24") (pin "1") (pinfunction "1_1") (pintype "passive"))
      (node (ref "C30") (pin "1") (pinfunction "1_1") (pintype "passive"))
      (node (ref "C33") (pin "1") (pinfunction "1_1") (pintype "passive"))
      (node (ref "C34") (pin "1") (pinfunction "1_1") (pintype "passive"))
      (node (ref "C35") (pin "1") (pinfunction "1_1") (pintype "passive"))
      (node (ref "C36") (pin "1") (pinfunction "1_1") (pintype "passive"))
      (node (ref "D1") (pin "C") (pinfunction "CATHODE_C") (pintype "bidirectional"))
      (node (ref "J9") (pin "P1") (pinfunction "P1_P1") (pintype "bidirectional"))
      (node (ref "Q3") (pin "D1") (pinfunction "D1_D1") (pintype "passive"))
      (node (ref "Q3") (pin "D2") (pinfunction "D1_D2") (pintype "passive"))
      (node (ref "Q3") (pin "D3") (pinfunction "D1_D3") (pintype "passive"))
      (node (ref "Q3") (pin "D4") (pinfunction "D1_D4") (pintype "passive"))
      (node (ref "Q3") (pin "D5") (pinfunction "D1_D5") (pintype "passive"))
      (node (ref "R32") (pin "2") (pinfunction "2_2") (pintype "passive"))
    )
    (net (code "5") (name "BATT_SENSE") (class "Default")
      (node (ref "R51") (pin "1") (pinfunction "1_1") (pintype "passive"))
      (node (ref "R52") (pin "2") (pinfunction "2_2") (pintype "passive"))
      (node (ref "U3") (pin "P$19") (pinfunction "ADC6_P$19") (pintype "bidirectional"))
    )
    (net (code "6") (name "BATT_SENSE_GUMSTIX") (class "Default")
      (node (ref "IC3") (pin "P47") (pinfunction "ADCIN4_P47") (pintype "bidirectional"))
      (node (ref "R39") (pin "1") (pinfunction "1_1") (pintype "passive"))
      (node (ref "R40") (pin "2") (pinfunction "2_2") (pintype "passive"))
    )
    (net (code "7") (name "BURN_1") (class "Default")
      (node (ref "U$15") (pin "1") (pinfunction "G_1") (pintype "passive"))
      (node (ref "U3") (pin "P$9") (pinfunction "(T1)PD5_P$9") (pintype "bidirectional"))
    )
    (net (code "8") (name "ENABLE") (class "Default")
      (node (ref "Q2") (pin "1") (pinfunction "G_1") (pintype "passive"))
      (node (ref "R26") (pin "2") (pinfunction "2_2") (pintype "passive"))
      (node (ref "R39") (pin "2") (pinfunction "2_2") (pintype "passive"))
      (node (ref "R51") (pin "2") (pinfunction "2_2") (pintype "passive"))
      (node (ref "R8") (pin "2") (pinfunction "2_2") (pintype "passive"))
      (node (ref "U$2") (pin "P$5") (pinfunction "P$5_P$5") (pintype "bidirectional"))
    )
    (net (code "9") (name "GND") (class "Default")
      (node (ref "C10") (pin "2") (pinfunction "2_2") (pintype "passive"))
      (node (ref "C11") (pin "2") (pinfunction "2_2") (pintype "passive"))
      (node (ref "C12") (pin "2") (pinfunction "2_2") (pintype "passive"))
      (node (ref "C13") (pin "2") (pinfunction "2_2") (pintype "passive"))
      (node (ref "C14") (pin "1") (pinfunction "1_1") (pintype "passive"))
      (node (ref "C15") (pin "1") (pinfunction "1_1") (pintype "passive"))
      (node (ref "C16") (pin "2") (pinfunction "2_2") (pintype "passive"))
      (node (ref "C18") (pin "2") (pinfunction "2_2") (pintype "passive"))
      (node (ref "C19") (pin "2") (pinfunction "2_2") (pintype "passive"))
      (node (ref "C2") (pin "C") (pinfunction "CATHODE_C") (pintype "bidirectional"))
      (node (ref "C20") (pin "2") (pinfunction "2_2") (pintype "passive"))
      (node (ref "C21") (pin "2") (pinfunction "2_2") (pintype "passive"))
      (node (ref "C22") (pin "2") (pinfunction "2_2") (pintype "passive"))
      (node (ref "C23") (pin "-") (pinfunction "-_-") (pintype "bidirectional"))
      (node (ref "C24") (pin "2") (pinfunction "2_2") (pintype "passive"))
      (node (ref "C25") (pin "2") (pinfunction "2_2") (pintype "passive"))
      (node (ref "C26") (pin "1") (pinfunction "1_1") (pintype "passive"))
      (node (ref "C27") (pin "1") (pinfunction "1_1") (pintype "passive"))
      (node (ref "C3") (pin "2") (pinfunction "2_2") (pintype "passive"))
      (node (ref "C30") (pin "2") (pinfunction "2_2") (pintype "passive"))
      (node (ref "C32") (pin "2") (pinfunction "2_2") (pintype "passive"))
      (node (ref "C33") (pin "2") (pinfunction "2_2") (pintype "passive"))
      (node (ref "C34") (pin "2") (pinfunction "2_2") (pintype "passive"))
      (node (ref "C35") (pin "2") (pinfunction "2_2") (pintype "passive"))
      (node (ref "C36") (pin "2") (pinfunction "2_2") (pintype "passive"))
      (node (ref "C4") (pin "2") (pinfunction "2_2") (pintype "passive"))
      (node (ref "C40") (pin "1") (pinfunction "1_1") (pintype "passive"))
      (node (ref "C41") (pin "1") (pinfunction "1_1") (pintype "passive"))
      (node (ref "C42") (pin "G") (pinfunction "CATHODE_G") (pintype "bidirectional"))
      (node (ref "C43") (pin "G") (pinfunction "CATHODE_G") (pintype "bidirectional"))
      (node (ref "C5") (pin "2") (pinfunction "2_2") (pintype "passive"))
      (node (ref "C7") (pin "2") (pinfunction "2_2") (pintype "passive"))
      (node (ref "C8") (pin "2") (pinfunction "2_2") (pintype "passive"))
      (node (ref "C9") (pin "2") (pinfunction "2_2") (pintype "passive"))
      (node (ref "IC3") (pin "P23") (pinfunction "GND(2)_P23") (pintype "bidirectional"))
      (node (ref "IC3") (pin "P33") (pinfunction "GND(1)_P33") (pintype "bidirectional"))
      (node (ref "IC3") (pin "P45") (pinfunction "AGND_P45") (pintype "bidirectional"))
      (node (ref "IC3") (pin "P9") (pinfunction "GND(3)_P9") (pintype "bidirectional"))
      (node (ref "J7") (pin "4") (pinfunction "P$4_4") (pintype "bidirectional"))
      (node (ref "J9") (pin "P2") (pinfunction "P2_P2") (pintype "bidirectional"))
      (node (ref "L2") (pin "2") (pinfunction "2_2") (pintype "bidirectional"))
      (node (ref "LED1") (pin "C") (pinfunction "C_C") (pintype "passive"))
      (node (ref "LED2") (pin "C") (pinfunction "C_C") (pintype "passive"))
      (node (ref "LED3") (pin "C") (pinfunction "C_C") (pintype "passive"))
      (node (ref "LED_M0") (pin "C") (pinfunction "C_C") (pintype "passive"))
      (node (ref "LED_M1") (pin "C") (pinfunction "C_C") (pintype "passive"))
      (node (ref "LED_M2") (pin "C") (pinfunction "C_C") (pintype "passive"))
      (node (ref "LED_M3") (pin "C") (pinfunction "C_C") (pintype "passive"))
      (node (ref "Q2") (pin "2") (pinfunction "S_2") (pintype "passive"))
      (node (ref "R12") (pin "2") (pinfunction "2_2") (pintype "passive"))
      (node (ref "R21") (pin "1") (pinfunction "1_1") (pintype "passive"))
      (node (ref "R26") (pin "1") (pinfunction "1_1") (pintype "passive"))
      (node (ref "R29") (pin "1") (pinfunction "1_1") (pintype "passive"))
      (node (ref "R33") (pin "1") (pinfunction "1_1") (pintype "passive"))
      (node (ref "R34") (pin "1") (pinfunction "1_1") (pintype "passive"))
      (node (ref "R35") (pin "1") (pinfunction "1_1") (pintype "passive"))
      (node (ref "R40") (pin "1") (pinfunction "1_1") (pintype "passive"))
      (node (ref "R52") (pin "1") (pinfunction "1_1") (pintype "passive"))
      (node (ref "S2") (pin "P$2") (pinfunction "P2_P$2") (pintype "bidirectional"))
      (node (ref "S2") (pin "P$4") (pinfunction "P4_P$4") (pintype "bidirectional"))
      (node (ref "SV1") (pin "1") (pinfunction "1_1") (pintype "passive"))
      (node (ref "SV2") (pin "GND") (pinfunction "GND_GND") (pintype "passive"))
      (node (ref "SV3") (pin "1") (pinfunction "1_1") (pintype "passive"))
      (node (ref "SV4") (pin "1") (pinfunction "1_1") (pintype "passive"))
      (node (ref "T11") (pin "2") (pinfunction "S_2") (pintype "passive"))
      (node (ref "U$10") (pin "3") (pinfunction "E_3") (pintype "passive"))
      (node (ref "U$11") (pin "P$1") (pinfunction "EN_P$1") (pintype "input"))
      (node (ref "U$11") (pin "P$12") (pinfunction "FORCEON_P$12") (pintype "input"))
      (node (ref "U$11") (pin "P$14") (pinfunction "GND_P$14") (pintype "power_in"))
      (node (ref "U$12") (pin "P$2") (pinfunction "P2_P$2") (pintype "bidirectional"))
      (node (ref "U$13") (pin "GND") (pinfunction "GND_GND") (pintype "power_in"))
      (node (ref "U$2") (pin "P$1") (pinfunction "P$1_P$1") (pintype "bidirectional"))
      (node (ref "U$2") (pin "P$4") (pinfunction "P$4_P$4") (pintype "bidirectional"))
      (node (ref "U$3") (pin "GND") (pinfunction "GND_GND") (pintype "bidirectional"))
      (node (ref "U$4") (pin "GND") (pinfunction "GND_GND") (pintype "bidirectional"))
      (node (ref "U$5") (pin "GND") (pinfunction "GND_GND") (pintype "bidirectional"))
      (node (ref "U$6") (pin "GND") (pinfunction "GND_GND") (pintype "bidirectional"))
      (node (ref "U$9") (pin "A") (pinfunction "A_A") (pintype "bidirectional"))
      (node (ref "U1") (pin "P$6") (pinfunction "GND_P$6") (pintype "bidirectional"))
      (node (ref "U2") (pin "P$10") (pinfunction "P$2_P$10") (pintype "bidirectional"))
      (node (ref "U2") (pin "P$11") (pinfunction "P$2_P$11") (pintype "bidirectional"))
      (node (ref "U2") (pin "P$12") (pinfunction "P$2_P$12") (pintype "bidirectional"))
      (node (ref "U2") (pin "P$13") (pinfunction "P$2_P$13") (pintype "bidirectional"))
      (node (ref "U2") (pin "P$6") (pinfunction "GND_P$6") (pintype "bidirectional"))
      (node (ref "U2") (pin "P$9") (pinfunction "PGND_P$9") (pintype "bidirectional"))
      (node (ref "U3") (pin "P$21") (pinfunction "AGND_P$21") (pintype "bidirectional"))
      (node (ref "U3") (pin "P$3") (pinfunction "GND_P$3") (pintype "bidirectional"))
      (node (ref "U3") (pin "P$5") (pinfunction "GND2_P$5") (pintype "bidirectional"))
      (node (ref "U4") (pin "P$3") (pinfunction "GND_P$3") (pintype "bidirectional"))
      (node (ref "U4") (pin "P$4") (pinfunction "/EN_P$4") (pintype "bidirectional"))
    )
    (net (code "10") (name "KILL_SIG") (class "Default")
      (node (ref "SV3") (pin "3") (pinfunction "3_3") (pintype "passive"))
      (node (ref "U3") (pin "P$23") (pinfunction "(ADC0)PC0_P$23") (pintype "bidirectional"))
    )
    (net (code "11") (name "LED1") (class "Default")
      (node (ref "R48") (pin "2") (pinfunction "2_2") (pintype "passive"))
      (node (ref "U3") (pin "P$13") (pinfunction "(OC1)PB1_P$13") (pintype "bidirectional"))
    )
    (net (code "12") (name "LED2") (class "Default")
      (node (ref "R47") (pin "2") (pinfunction "2_2") (pintype "passive"))
      (node (ref "U3") (pin "P$12") (pinfunction "(ICP)PB0_P$12") (pintype "bidirectional"))
    )
    (net (code "13") (name "LED3") (class "Default")
      (node (ref "R44") (pin "2") (pinfunction "2_2") (pintype "passive"))
      (node (ref "U3") (pin "P$2") (pinfunction "(T0)PD4_P$2") (pintype "bidirectional"))
    )
    (net (code "14") (name "MISO") (class "Default")
      (node (ref "SV2") (pin "MISO") (pinfunction "MISO_MISO") (pintype "passive"))
      (node (ref "U3") (pin "P$16") (pinfunction "(MISO)PB4_P$16") (pintype "bidirectional"))
    )
    (net (code "15") (name "MOSI") (class "Default")
      (node (ref "SV2") (pin "MOSI") (pinfunction "MOSI_MOSI") (pintype "passive"))
      (node (ref "U3") (pin "P$15") (pinfunction "(MOSI)PB3_P$15") (pintype "bidirectional"))
    )
    (net (code "16") (name "MOTOR0_PWM_1V8") (class "Default")
      (node (ref "IC3") (pin "P37") (pinfunction "GPIO147/PWM8_P37") (pintype "bidirectional"))
      (node (ref "R19") (pin "1") (pinfunction "1_1") (pintype "passive"))
      (node (ref "T10") (pin "2") (pinfunction "S_2") (pintype "passive"))
    )
    (net (code "17") (name "MOTOR1_PWM_1V8") (class "Default")
      (node (ref "IC3") (pin "P38") (pinfunction "GPIO144/PWM9_P38") (pintype "bidirectional"))
      (node (ref "R13") (pin "1") (pinfunction "1_1") (pintype "passive"))
      (node (ref "T7") (pin "2") (pinfunction "S_2") (pintype "passive"))
    )
    (net (code "18") (name "MOTOR2_PWM_1V8") (class "Default")
      (node (ref "IC3") (pin "P36") (pinfunction "GPIO145/PWM10_P36") (pintype "bidirectional"))
      (node (ref "R15") (pin "1") (pinfunction "1_1") (pintype "passive"))
      (node (ref "T8") (pin "2") (pinfunction "S_2") (pintype "passive"))
    )
    (net (code "19") (name "MOTOR3_PWM_1V8") (class "Default")
      (node (ref "IC3") (pin "P35") (pinfunction "GPIO146/PWM11_P35") (pintype "bidirectional"))
      (node (ref "R17") (pin "1") (pinfunction "1_1") (pintype "passive"))
      (node (ref "T9") (pin "2") (pinfunction "S_2") (pintype "passive"))
    )
    (net (code "20") (name "MOTOR_ENABLE") (class "Default")
      (node (ref "Q4") (pin "G") (pinfunction "G_G") (pintype "passive"))
      (node (ref "Q5") (pin "G") (pinfunction "G_G") (pintype "passive"))
      (node (ref "Q6") (pin "G") (pinfunction "G_G") (pintype "passive"))
      (node (ref "Q7") (pin "G") (pinfunction "G_G") (pintype "passive"))
      (node (ref "R5") (pin "2") (pinfunction "2_2") (pintype "passive"))
      (node (ref "R8") (pin "1") (pinfunction "1_1") (pintype "passive"))
    )
    (net (code "21") (name "MOTOR_LOGIC") (class "Default")
      (node (ref "R21") (pin "2") (pinfunction "2_2") (pintype "passive"))
      (node (ref "T11") (pin "1") (pinfunction "G_1") (pintype "passive"))
      (node (ref "U3") (pin "P$11") (pinfunction "(AIN1)PD7_P$11") (pintype "bidirectional"))
    )
    (net (code "22") (name "N$39") (class "Default")
      (node (ref "U3") (pin "P$10") (pinfunction "(AIN0)PD6_P$10") (pintype "bidirectional"))
    )
    (net (code "23") (name "N$41") (class "Default")
      (node (ref "U3") (pin "P$32") (pinfunction "(INT0)PD2_P$32") (pintype "bidirectional"))
    )
    (net (code "24") (name "Net-(C17-Pad2)") (class "Default")
      (node (ref "C17") (pin "2") (pinfunction "2_2") (pintype "passive"))
      (node (ref "R27") (pin "1") (pinfunction "1_1") (pintype "passive"))
    )
    (net (code "25") (name "Net-(C31-Pad2)") (class "Default")
      (node (ref "C31") (pin "2") (pinfunction "2_2") (pintype "passive"))
      (node (ref "D1") (pin "A1") (pinfunction "ANODE_A1") (pintype "bidirectional"))
      (node (ref "D1") (pin "A2") (pinfunction "ANODE_A2") (pintype "bidirectional"))
      (node (ref "L2") (pin "4") (pinfunction "4_4") (pintype "bidirectional"))
    )
    (net (code "26") (name "Net-(LED1-PadA)") (class "Default")
      (node (ref "LED1") (pin "A") (pinfunction "A_A") (pintype "passive"))
      (node (ref "R44") (pin "1") (pinfunction "1_1") (pintype "passive"))
    )
    (net (code "27") (name "Net-(LED2-PadA)") (class "Default")
      (node (ref "LED2") (pin "A") (pinfunction "A_A") (pintype "passive"))
      (node (ref "R47") (pin "1") (pinfunction "1_1") (pintype "passive"))
    )
    (net (code "28") (name "Net-(LED3-PadA)") (class "Default")
      (node (ref "LED3") (pin "A") (pinfunction "A_A") (pintype "passive"))
      (node (ref "R48") (pin "1") (pinfunction "1_1") (pintype "passive"))
    )
    (net (code "29") (name "Net-(LED_M0-PadA)") (class "Default")
      (node (ref "LED_M0") (pin "A") (pinfunction "A_A") (pintype "passive"))
      (node (ref "R24") (pin "1") (pinfunction "1_1") (pintype "passive"))
    )
    (net (code "30") (name "Net-(LED_M1-PadA)") (class "Default")
      (node (ref "LED_M1") (pin "A") (pinfunction "A_A") (pintype "passive"))
      (node (ref "R6") (pin "1") (pinfunction "1_1") (pintype "passive"))
    )
    (net (code "31") (name "Net-(LED_M2-PadA)") (class "Default")
      (node (ref "LED_M2") (pin "A") (pinfunction "A_A") (pintype "passive"))
      (node (ref "R22") (pin "1") (pinfunction "1_1") (pintype "passive"))
    )
    (net (code "32") (name "Net-(LED_M3-PadA)") (class "Default")
      (node (ref "LED_M3") (pin "A") (pinfunction "A_A") (pintype "passive"))
      (node (ref "R23") (pin "1") (pinfunction "1_1") (pintype "passive"))
    )
    (net (code "33") (name "Net-(Q1-P$1)") (class "Default")
      (node (ref "C15") (pin "2") (pinfunction "2_2") (pintype "passive"))
      (node (ref "Q1") (pin "X1") (pinfunction "P$1_X1") (pintype "bidirectional"))
      (node (ref "U3") (pin "P$7") (pinfunction "XTAL1_P$7") (pintype "bidirectional"))
    )
    (net (code "34") (name "Net-(Q1-P$2)") (class "Default")
      (node (ref "C14") (pin "2") (pinfunction "2_2") (pintype "passive"))
      (node (ref "Q1") (pin "X2") (pinfunction "P$2_X2") (pintype "bidirectional"))
      (node (ref "U3") (pin "P$8") (pinfunction "XTAL2_P$8") (pintype "bidirectional"))
    )
    (net (code "35") (name "Net-(Q2-D)") (class "Default")
      (node (ref "Q2") (pin "3") (pinfunction "D_3") (pintype "passive"))
      (node (ref "Q3") (pin "G") (pinfunction "G_G") (pintype "passive"))
      (node (ref "R3") (pin "1") (pinfunction "1_1") (pintype "passive"))
    )
    (net (code "36") (name "Net-(Q4-D1-PadD2)") (class "Default")
      (node (ref "Q4") (pin "D1") (pinfunction "D1_D1") (pintype "passive"))
      (node (ref "Q4") (pin "D2") (pinfunction "D1_D2") (pintype "passive"))
      (node (ref "Q4") (pin "D3") (pinfunction "D1_D3") (pintype "passive"))
      (node (ref "Q4") (pin "D4") (pinfunction "D1_D4") (pintype "passive"))
      (node (ref "Q4") (pin "D5") (pinfunction "D1_D5") (pintype "passive"))
      (node (ref "R24") (pin "2") (pinfunction "2_2") (pintype "passive"))
      (node (ref "U$3") (pin "BATT") (pinfunction "BATT_BATT") (pintype "bidirectional"))
    )
    (net (code "37") (name "Net-(Q5-D1-PadD2)") (class "Default")
      (node (ref "Q5") (pin "D1") (pinfunction "D1_D1") (pintype "passive"))
      (node (ref "Q5") (pin "D2") (pinfunction "D1_D2") (pintype "passive"))
      (node (ref "Q5") (pin "D3") (pinfunction "D1_D3") (pintype "passive"))
      (node (ref "Q5") (pin "D4") (pinfunction "D1_D4") (pintype "passive"))
      (node (ref "Q5") (pin "D5") (pinfunction "D1_D5") (pintype "passive"))
      (node (ref "R6") (pin "2") (pinfunction "2_2") (pintype "passive"))
      (node (ref "U$4") (pin "BATT") (pinfunction "BATT_BATT") (pintype "bidirectional"))
    )
    (net (code "38") (name "Net-(Q6-D1-PadD2)") (class "Default")
      (node (ref "Q6") (pin "D1") (pinfunction "D1_D1") (pintype "passive"))
      (node (ref "Q6") (pin "D2") (pinfunction "D1_D2") (pintype "passive"))
      (node (ref "Q6") (pin "D3") (pinfunction "D1_D3") (pintype "passive"))
      (node (ref "Q6") (pin "D4") (pinfunction "D1_D4") (pintype "passive"))
      (node (ref "Q6") (pin "D5") (pinfunction "D1_D5") (pintype "passive"))
      (node (ref "R22") (pin "2") (pinfunction "2_2") (pintype "passive"))
      (node (ref "U$5") (pin "BATT") (pinfunction "BATT_BATT") (pintype "bidirectional"))
    )
    (net (code "39") (name "Net-(Q7-D1-PadD2)") (class "Default")
      (node (ref "Q7") (pin "D1") (pinfunction "D1_D1") (pintype "passive"))
      (node (ref "Q7") (pin "D2") (pinfunction "D1_D2") (pintype "passive"))
      (node (ref "Q7") (pin "D3") (pinfunction "D1_D3") (pintype "passive"))
      (node (ref "Q7") (pin "D4") (pinfunction "D1_D4") (pintype "passive"))
      (node (ref "Q7") (pin "D5") (pinfunction "D1_D5") (pintype "passive"))
      (node (ref "R23") (pin "2") (pinfunction "2_2") (pintype "passive"))
      (node (ref "U$6") (pin "BATT") (pinfunction "BATT_BATT") (pintype "bidirectional"))
    )
    (net (code "40") (name "Net-(Q8-D)") (class "Default")
      (node (ref "C31") (pin "1") (pinfunction "1_1") (pintype "passive"))
      (node (ref "L2") (pin "3") (pinfunction "3_3") (pintype "bidirectional"))
      (node (ref "Q8") (pin "P$5") (pinfunction "D_P$5") (pintype "bidirectional"))
    )
    (net (code "41") (name "Net-(Q8-G)") (class "Default")
      (node (ref "Q8") (pin "P$4") (pinfunction "G_P$4") (pintype "bidirectional"))
      (node (ref "R4") (pin "2") (pinfunction "2_2") (pintype "passive"))
    )
    (net (code "42") (name "Net-(Q8-S-PadP$1)") (class "Default")
      (node (ref "Q8") (pin "P$1") (pinfunction "S_P$1") (pintype "bidirectional"))
      (node (ref "Q8") (pin "P$2") (pinfunction "S_P$2") (pintype "bidirectional"))
      (node (ref "Q8") (pin "P$3") (pinfunction "S_P$3") (pintype "bidirectional"))
      (node (ref "R30") (pin "2") (pinfunction "2_2") (pintype "passive"))
      (node (ref "R35") (pin "2") (pinfunction "2_2") (pintype "passive"))
    )
    (net (code "43") (name "Net-(R31-Pad2)") (class "Default")
      (node (ref "R31") (pin "2") (pinfunction "2_2") (pintype "passive"))
      (node (ref "R32") (pin "1") (pinfunction "1_1") (pintype "passive"))
    )
    (net (code "44") (name "Net-(SJ1-Pad2)") (class "Default")
      (node (ref "SJ1") (pin "2") (pinfunction "2_2") (pintype "passive"))
      (node (ref "U$4") (pin "SDA/C+") (pinfunction "SDA/C+_SDA/C+") (pintype "bidirectional"))
    )
    (net (code "45") (name "Net-(SJ2-Pad2)") (class "Default")
      (node (ref "SJ2") (pin "2") (pinfunction "2_2") (pintype "passive"))
      (node (ref "U$3") (pin "SDA/C+") (pinfunction "SDA/C+_SDA/C+") (pintype "bidirectional"))
    )
    (net (code "46") (name "Net-(SJ3-Pad2)") (class "Default")
      (node (ref "SJ3") (pin "2") (pinfunction "2_2") (pintype "passive"))
      (node (ref "U$3") (pin "SCL/C-") (pinfunction "SCL/C-_SCL/C-") (pintype "bidirectional"))
    )
    (net (code "47") (name "Net-(SJ4-Pad2)") (class "Default")
      (node (ref "SJ4") (pin "2") (pinfunction "2_2") (pintype "passive"))
      (node (ref "U$4") (pin "SCL/C-") (pinfunction "SCL/C-_SCL/C-") (pintype "bidirectional"))
    )
    (net (code "48") (name "Net-(SJ5-Pad2)") (class "Default")
      (node (ref "SJ5") (pin "2") (pinfunction "2_2") (pintype "passive"))
      (node (ref "U$5") (pin "SDA/C+") (pinfunction "SDA/C+_SDA/C+") (pintype "bidirectional"))
    )
    (net (code "49") (name "Net-(SJ6-Pad2)") (class "Default")
      (node (ref "SJ6") (pin "2") (pinfunction "2_2") (pintype "passive"))
      (node (ref "U$5") (pin "SCL/C-") (pinfunction "SCL/C-_SCL/C-") (pintype "bidirectional"))
    )
    (net (code "50") (name "Net-(SJ7-Pad2)") (class "Default")
      (node (ref "SJ7") (pin "2") (pinfunction "2_2") (pintype "passive"))
      (node (ref "U$6") (pin "SDA/C+") (pinfunction "SDA/C+_SDA/C+") (pintype "bidirectional"))
    )
    (net (code "51") (name "Net-(SJ8-Pad2)") (class "Default")
      (node (ref "SJ8") (pin "2") (pinfunction "2_2") (pintype "passive"))
      (node (ref "U$6") (pin "SCL/C-") (pinfunction "SCL/C-_SCL/C-") (pintype "bidirectional"))
    )
    (net (code "52") (name "Net-(T11-D)") (class "Default")
      (node (ref "R5") (pin "1") (pinfunction "1_1") (pintype "passive"))
      (node (ref "T11") (pin "3") (pinfunction "D_3") (pintype "passive"))
    )
    (net (code "53") (name "Net-(U$1-1)") (class "Default")
      (node (ref "C6") (pin "2") (pinfunction "2_2") (pintype "passive"))
      (node (ref "U$1") (pin "P1") (pinfunction "1_P1") (pintype "bidirectional"))
      (node (ref "U$9") (pin "C") (pinfunction "C_C") (pintype "bidirectional"))
      (node (ref "U2") (pin "P$8") (pinfunction "PH_P$8") (pintype "bidirectional"))
    )
    (net (code "54") (name "Net-(U$10-B)") (class "Default")
      (node (ref "R41") (pin "1") (pinfunction "1_1") (pintype "passive"))
      (node (ref "U$10") (pin "1") (pinfunction "B_1") (pintype "passive"))
    )
    (net (code "55") (name "Net-(U$10-C)") (class "Default")
      (node (ref "U$10") (pin "TAB") (pinfunction "C_TAB") (pintype "passive"))
      (node (ref "U$14") (pin "P$2") (pinfunction "4_P$2") (pintype "passive"))
    )
    (net (code "56") (name "Net-(U$11-C1+)") (class "Default")
      (node (ref "C37") (pin "1") (pinfunction "1_1") (pintype "passive"))
      (node (ref "U$11") (pin "P$2") (pinfunction "C1+_P$2") (pintype "passive"))
    )
    (net (code "57") (name "Net-(U$11-C1-)") (class "Default")
      (node (ref "C37") (pin "2") (pinfunction "2_2") (pintype "passive"))
      (node (ref "U$11") (pin "P$4") (pinfunction "C1-_P$4") (pintype "passive"))
    )
    (net (code "58") (name "Net-(U$11-C2+)") (class "Default")
      (node (ref "C38") (pin "1") (pinfunction "1_1") (pintype "passive"))
      (node (ref "U$11") (pin "P$5") (pinfunction "C2+_P$5") (pintype "passive"))
    )
    (net (code "59") (name "Net-(U$11-C2-)") (class "Default")
      (node (ref "C38") (pin "2") (pinfunction "2_2") (pintype "passive"))
      (node (ref "U$11") (pin "P$6") (pinfunction "C2-_P$6") (pintype "passive"))
    )
    (net (code "60") (name "Net-(U$11-V+)") (class "Default")
      (node (ref "C39") (pin "2") (pinfunction "2_2") (pintype "passive"))
      (node (ref "U$11") (pin "P$3") (pinfunction "V+_P$3") (pintype "passive"))
    )
    (net (code "61") (name "Net-(U$11-V-)") (class "Default")
      (node (ref "C40") (pin "2") (pinfunction "2_2") (pintype "passive"))
      (node (ref "U$11") (pin "P$7") (pinfunction "V-_P$7") (pintype "passive"))
    )
    (net (code "62") (name "Net-(U$15-S)") (class "Default")
      (node (ref "R41") (pin "2") (pinfunction "2_2") (pintype "passive"))
      (node (ref "U$15") (pin "2") (pinfunction "S_2") (pintype "passive"))
    )
    (net (code "63") (name "Net-(U1-COMP)") (class "Default")
      (node (ref "C1") (pin "1") (pinfunction "1_1") (pintype "passive"))
      (node (ref "C17") (pin "1") (pinfunction "1_1") (pintype "passive"))
      (node (ref "U1") (pin "P$3") (pinfunction "COMP_P$3") (pintype "bidirectional"))
    )
    (net (code "64") (name "Net-(U1-CS)") (class "Default")
      (node (ref "C22") (pin "1") (pinfunction "1_1") (pintype "passive"))
      (node (ref "R30") (pin "1") (pinfunction "1_1") (pintype "passive"))
      (node (ref "U1") (pin "P$8") (pinfunction "CS_P$8") (pintype "bidirectional"))
    )
    (net (code "65") (name "Net-(U1-FB)") (class "Default")
      (node (ref "C1") (pin "2") (pinfunction "2_2") (pintype "passive"))
      (node (ref "R27") (pin "2") (pinfunction "2_2") (pintype "passive"))
      (node (ref "R31") (pin "1") (pinfunction "1_1") (pintype "passive"))
      (node (ref "R33") (pin "2") (pinfunction "2_2") (pintype "passive"))
      (node (ref "U1") (pin "P$2") (pinfunction "FB_P$2") (pintype "bidirectional"))
    )
    (net (code "66") (name "Net-(U1-OUT)") (class "Default")
      (node (ref "R4") (pin "1") (pinfunction "1_1") (pintype "passive"))
      (node (ref "U1") (pin "P$5") (pinfunction "OUT_P$5") (pintype "bidirectional"))
    )
    (net (code "67") (name "Net-(U1-RT)") (class "Default")
      (node (ref "R34") (pin "2") (pinfunction "2_2") (pintype "passive"))
      (node (ref "U1") (pin "P$9") (pinfunction "RT_P$9") (pintype "bidirectional"))
    )
    (net (code "68") (name "Net-(U1-SS)") (class "Default")
      (node (ref "C32") (pin "1") (pinfunction "1_1") (pintype "passive"))
      (node (ref "U1") (pin "P$10") (pinfunction "SS_P$10") (pintype "bidirectional"))
    )
    (net (code "69") (name "Net-(U1-UVLO)") (class "Default")
      (node (ref "R28") (pin "1") (pinfunction "1_1") (pintype "passive"))
      (node (ref "R29") (pin "2") (pinfunction "2_2") (pintype "passive"))
      (node (ref "U1") (pin "P$7") (pinfunction "UVLO_P$7") (pintype "bidirectional"))
    )
    (net (code "70") (name "Net-(U1-VCC)") (class "Default")
      (node (ref "C18") (pin "1") (pinfunction "1_1") (pintype "passive"))
      (node (ref "U1") (pin "P$4") (pinfunction "VCC_P$4") (pintype "bidirectional"))
    )
    (net (code "71") (name "Net-(U2A-BOOT)") (class "Default")
      (node (ref "C6") (pin "1") (pinfunction "1_1") (pintype "passive"))
      (node (ref "U2") (pin "P$1") (pinfunction "BOOT_P$1") (pintype "bidirectional"))
    )
    (net (code "72") (name "Net-(U2A-ENA)") (class "Default")
      (node (ref "U$2") (pin "P$2") (pinfunction "P$2_P$2") (pintype "bidirectional"))
      (node (ref "U2") (pin "P$5") (pinfunction "ENA_P$5") (pintype "bidirectional"))
    )
    (net (code "73") (name "Net-(U2A-VSNS)") (class "Default")
      (node (ref "R11") (pin "1") (pinfunction "1_1") (pintype "passive"))
      (node (ref "R12") (pin "1") (pinfunction "1_1") (pintype "passive"))
      (node (ref "U2") (pin "P$4") (pinfunction "VSNS_P$4") (pintype "bidirectional"))
    )
    (net (code "74") (name "Net-(U3-AREF)") (class "Default")
      (node (ref "C12") (pin "1") (pinfunction "1_1") (pintype "passive"))
      (node (ref "U3") (pin "P$20") (pinfunction "AREF_P$20") (pintype "bidirectional"))
    )
    (net (code "75") (name "PWM_5V_M0") (class "Default")
      (node (ref "R20") (pin "1") (pinfunction "1_1") (pintype "passive"))
      (node (ref "SJ3") (pin "1") (pinfunction "1_1") (pintype "passive"))
      (node (ref "T10") (pin "3") (pinfunction "D_3") (pintype "passive"))
    )
    (net (code "76") (name "PWM_5V_M1") (class "Default")
      (node (ref "R14") (pin "1") (pinfunction "1_1") (pintype "passive"))
      (node (ref "SJ4") (pin "1") (pinfunction "1_1") (pintype "passive"))
      (node (ref "T7") (pin "3") (pinfunction "D_3") (pintype "passive"))
    )
    (net (code "77") (name "PWM_5V_M2") (class "Default")
      (node (ref "R16") (pin "1") (pinfunction "1_1") (pintype "passive"))
      (node (ref "SJ6") (pin "1") (pinfunction "1_1") (pintype "passive"))
      (node (ref "T8") (pin "3") (pinfunction "D_3") (pintype "passive"))
    )
    (net (code "78") (name "PWM_5V_M3") (class "Default")
      (node (ref "R18") (pin "1") (pinfunction "1_1") (pintype "passive"))
      (node (ref "SJ8") (pin "1") (pinfunction "1_1") (pintype "passive"))
      (node (ref "T9") (pin "3") (pinfunction "D_3") (pintype "passive"))
    )
    (net (code "79") (name "RESET") (class "Default")
      (node (ref "R7") (pin "1") (pinfunction "1_1") (pintype "passive"))
      (node (ref "S2") (pin "P$1") (pinfunction "P1_P$1") (pintype "bidirectional"))
      (node (ref "S2") (pin "P$3") (pinfunction "P3_P$3") (pintype "bidirectional"))
      (node (ref "SV2") (pin "RESET") (pinfunction "RESET_RESET") (pintype "passive"))
      (node (ref "U3") (pin "P$29") (pinfunction "RESET_P$29") (pintype "bidirectional"))
    )
    (net (code "80") (name "RS-232_RX1") (class "Default")
      (node (ref "J7") (pin "3") (pinfunction "P$3_3") (pintype "bidirectional"))
      (node (ref "U$11") (pin "P$8") (pinfunction "RIN_P$8") (pintype "input"))
    )
    (net (code "81") (name "RS-232_TX1") (class "Default")
      (node (ref "J7") (pin "2") (pinfunction "P$2_2") (pintype "bidirectional"))
      (node (ref "U$11") (pin "P$13") (pinfunction "DOUT_P$13") (pintype "output"))
    )
    (net (code "82") (name "RX1_1V8") (class "Default")
      (node (ref "IC3") (pin "P17") (pinfunction "GPIO151/RXD1_P17") (pintype "bidirectional"))
      (node (ref "R25") (pin "1") (pinfunction "1_1") (pintype "passive"))
      (node (ref "T1") (pin "2") (pinfunction "S_2") (pintype "passive"))
    )
    (net (code "83") (name "RX1_5V") (class "Default")
      (node (ref "R36") (pin "1") (pinfunction "1_1") (pintype "passive"))
      (node (ref "T1") (pin "3") (pinfunction "D_3") (pintype "passive"))
      (node (ref "U$11") (pin "P$9") (pinfunction "ROUT_P$9") (pintype "output"))
    )
    (net (code "84") (name "SCK") (class "Default")
      (node (ref "SV2") (pin "SCK") (pinfunction "SCK_SCK") (pintype "passive"))
      (node (ref "U3") (pin "P$17") (pinfunction "(SCK)PB5_P$17") (pintype "bidirectional"))
    )
    (net (code "85") (name "SCL_1V8") (class "Default")
      (node (ref "IC3") (pin "P31") (pinfunction "GPIO184/SCL_P31") (pintype "bidirectional"))
      (node (ref "R1") (pin "1") (pinfunction "1_1") (pintype "passive"))
      (node (ref "T3") (pin "2") (pinfunction "S_2") (pintype "passive"))
    )
    (net (code "86") (name "SCL_5V") (class "Default")
      (node (ref "R2") (pin "1") (pinfunction "1_1") (pintype "passive"))
      (node (ref "SJ3") (pin "3") (pinfunction "3_3") (pintype "passive"))
      (node (ref "SJ4") (pin "3") (pinfunction "3_3") (pintype "passive"))
      (node (ref "SJ6") (pin "3") (pinfunction "3_3") (pintype "passive"))
      (node (ref "SJ8") (pin "3") (pinfunction "3_3") (pintype "passive"))
      (node (ref "SV1") (pin "4") (pinfunction "4_4") (pintype "passive"))
      (node (ref "T3") (pin "3") (pinfunction "D_3") (pintype "passive"))
      (node (ref "U3") (pin "P$28") (pinfunction "(ADC5)PC5_P$28") (pintype "bidirectional"))
    )
    (net (code "87") (name "SDA_1V8") (class "Default")
      (node (ref "IC3") (pin "P32") (pinfunction "GPIO185/SDA_P32") (pintype "bidirectional"))
      (node (ref "R9") (pin "1") (pinfunction "1_1") (pintype "passive"))
      (node (ref "T4") (pin "2") (pinfunction "S_2") (pintype "passive"))
    )
    (net (code "88") (name "SDA_5V") (class "Default")
      (node (ref "R10") (pin "1") (pinfunction "1_1") (pintype "passive"))
      (node (ref "SJ1") (pin "1") (pinfunction "1_1") (pintype "passive"))
      (node (ref "SJ2") (pin "1") (pinfunction "1_1") (pintype "passive"))
      (node (ref "SJ5") (pin "1") (pinfunction "1_1") (pintype "passive"))
      (node (ref "SJ7") (pin "1") (pinfunction "1_1") (pintype "passive"))
      (node (ref "SV1") (pin "3") (pinfunction "3_3") (pintype "passive"))
      (node (ref "T4") (pin "3") (pinfunction "D_3") (pintype "passive"))
      (node (ref "U3") (pin "P$27") (pinfunction "(ADC4)PC4_P$27") (pintype "bidirectional"))
    )
    (net (code "89") (name "SERVO_1") (class "Default")
      (node (ref "SV4") (pin "3") (pinfunction "3_3") (pintype "passive"))
      (node (ref "U3") (pin "P$1") (pinfunction "(INT1)PD3_P$1") (pintype "bidirectional"))
    )
    (net (code "90") (name "TX1_1V8") (class "Default")
      (node (ref "IC3") (pin "P18") (pinfunction "GPIO148/TXD1_P18") (pintype "bidirectional"))
      (node (ref "R37") (pin "1") (pinfunction "1_1") (pintype "passive"))
      (node (ref "T2") (pin "2") (pinfunction "S_2") (pintype "passive"))
    )
    (net (code "91") (name "TX1_5V") (class "Default")
      (node (ref "R38") (pin "1") (pinfunction "1_1") (pintype "passive"))
      (node (ref "T2") (pin "3") (pinfunction "D_3") (pintype "passive"))
      (node (ref "U$11") (pin "P$11") (pinfunction "DIN_P$11") (pintype "input"))
    )
    (net (code "92") (name "V_BATT") (class "Default")
      (node (ref "C19") (pin "1") (pinfunction "1_1") (pintype "passive"))
      (node (ref "C20") (pin "1") (pinfunction "1_1") (pintype "passive"))
      (node (ref "C21") (pin "1") (pinfunction "1_1") (pintype "passive"))
      (node (ref "C25") (pin "1") (pinfunction "1_1") (pintype "passive"))
      (node (ref "C3") (pin "1") (pinfunction "1_1") (pintype "passive"))
      (node (ref "C4") (pin "1") (pinfunction "1_1") (pintype "passive"))
      (node (ref "C42") (pin "P") (pinfunction "ANODE_P") (pintype "bidirectional"))
      (node (ref "C43") (pin "P") (pinfunction "ANODE_P") (pintype "bidirectional"))
      (node (ref "C5") (pin "1") (pinfunction "1_1") (pintype "passive"))
      (node (ref "L2") (pin "1") (pinfunction "1_1") (pintype "bidirectional"))
      (node (ref "Q3") (pin "S1") (pinfunction "S1_S1") (pintype "passive"))
      (node (ref "Q3") (pin "S2") (pinfunction "S1_S2") (pintype "passive"))
      (node (ref "Q3") (pin "S3") (pinfunction "S1_S3") (pintype "passive"))
      (node (ref "Q4") (pin "S1") (pinfunction "S1_S1") (pintype "passive"))
      (node (ref "Q4") (pin "S2") (pinfunction "S1_S2") (pintype "passive"))
      (node (ref "Q4") (pin "S3") (pinfunction "S1_S3") (pintype "passive"))
      (node (ref "Q5") (pin "S1") (pinfunction "S1_S1") (pintype "passive"))
      (node (ref "Q5") (pin "S2") (pinfunction "S1_S2") (pintype "passive"))
      (node (ref "Q5") (pin "S3") (pinfunction "S1_S3") (pintype "passive"))
      (node (ref "Q6") (pin "S1") (pinfunction "S1_S1") (pintype "passive"))
      (node (ref "Q6") (pin "S2") (pinfunction "S1_S2") (pintype "passive"))
      (node (ref "Q6") (pin "S3") (pinfunction "S1_S3") (pintype "passive"))
      (node (ref "Q7") (pin "S1") (pinfunction "S1_S1") (pintype "passive"))
      (node (ref "Q7") (pin "S2") (pinfunction "S1_S2") (pintype "passive"))
      (node (ref "Q7") (pin "S3") (pinfunction "S1_S3") (pintype "passive"))
      (node (ref "R28") (pin "2") (pinfunction "2_2") (pintype "passive"))
      (node (ref "R3") (pin "2") (pinfunction "2_2") (pintype "passive"))
      (node (ref "U$13") (pin "BATT") (pinfunction "BATT_BATT") (pintype "power_in"))
      (node (ref "U$14") (pin "P$1") (pinfunction "3_P$1") (pintype "passive"))
      (node (ref "U$2") (pin "P$6") (pinfunction "P$6_P$6") (pintype "bidirectional"))
      (node (ref "U1") (pin "P$1") (pinfunction "VIN_P$1") (pintype "bidirectional"))
      (node (ref "U2") (pin "P$7") (pinfunction "VIN_P$7") (pintype "bidirectional"))
    )
    (net (code "93") (name "unconnected-(IC3-ADCIN2-PadP42)") (class "Default")
      (node (ref "IC3") (pin "P42") (pinfunction "ADCIN2_P42") (pintype "bidirectional"))
    )
    (net (code "94") (name "unconnected-(IC3-ADCIN3-PadP46)") (class "Default")
      (node (ref "IC3") (pin "P46") (pinfunction "ADCIN3_P46") (pintype "bidirectional"))
    )
    (net (code "95") (name "unconnected-(IC3-ADCIN5-PadP44)") (class "Default")
      (node (ref "IC3") (pin "P44") (pinfunction "ADCIN5_P44") (pintype "bidirectional"))
    )
    (net (code "96") (name "unconnected-(IC3-ADCIN6-PadP43)") (class "Default")
      (node (ref "IC3") (pin "P43") (pinfunction "ADCIN6_P43") (pintype "bidirectional"))
    )
    (net (code "97") (name "unconnected-(IC3-ADCIN7-PadP41)") (class "Default")
      (node (ref "IC3") (pin "P41") (pinfunction "ADCIN7_P41") (pintype "bidirectional"))
    )
    (net (code "98") (name "unconnected-(IC3-GPIO0{slash}WAKEUP-PadP21)") (class "Default")
      (node (ref "IC3") (pin "P21") (pinfunction "GPIO0/WAKEUP_P21") (pintype "bidirectional"))
    )
    (net (code "99") (name "unconnected-(IC3-GPIO10-PadP26)") (class "Default")
      (node (ref "IC3") (pin "P26") (pinfunction "GPIO10_P26") (pintype "bidirectional"))
    )
    (net (code "100") (name "unconnected-(IC3-GPIO13(1)-PadP52)") (class "Default")
      (node (ref "IC3") (pin "P52") (pinfunction "GPIO13(1)_P52") (pintype "bidirectional"))
    )
    (net (code "101") (name "unconnected-(IC3-GPIO13(2)-PadP51)") (class "Default")
      (node (ref "IC3") (pin "P51") (pinfunction "GPIO13(2)_P51") (pintype "bidirectional"))
    )
    (net (code "102") (name "unconnected-(IC3-GPIO14-PadP56)") (class "Default")
      (node (ref "IC3") (pin "P56") (pinfunction "GPIO14_P56") (pintype "bidirectional"))
    )
    (net (code "103") (name "unconnected-(IC3-GPIO17-PadP57)") (class "Default")
      (node (ref "IC3") (pin "P57") (pinfunction "GPIO17_P57") (pintype "bidirectional"))
    )
    (net (code "104") (name "unconnected-(IC3-GPIO18-PadP60)") (class "Default")
      (node (ref "IC3") (pin "P60") (pinfunction "GPIO18_P60") (pintype "bidirectional"))
    )
    (net (code "105") (name "unconnected-(IC3-GPIO19-PadP59)") (class "Default")
      (node (ref "IC3") (pin "P59") (pinfunction "GPIO19_P59") (pintype "bidirectional"))
    )
    (net (code "106") (name "unconnected-(IC3-GPIO20-PadP58)") (class "Default")
      (node (ref "IC3") (pin "P58") (pinfunction "GPIO20_P58") (pintype "bidirectional"))
    )
    (net (code "107") (name "unconnected-(IC3-GPIO21-PadP53)") (class "Default")
      (node (ref "IC3") (pin "P53") (pinfunction "GPIO21_P53") (pintype "bidirectional"))
    )
    (net (code "108") (name "unconnected-(IC3-GPIO22-PadP54)") (class "Default")
      (node (ref "IC3") (pin "P54") (pinfunction "GPIO22_P54") (pintype "bidirectional"))
    )
    (net (code "109") (name "unconnected-(IC3-GPIO23-PadP55)") (class "Default")
      (node (ref "IC3") (pin "P55") (pinfunction "GPIO23_P55") (pintype "bidirectional"))
    )
    (net (code "110") (name "unconnected-(IC3-GPIO64-PadP4)") (class "Default")
      (node (ref "IC3") (pin "P4") (pinfunction "GPIO64_P4") (pintype "bidirectional"))
    )
    (net (code "111") (name "unconnected-(IC3-GPIO65-PadP8)") (class "Default")
      (node (ref "IC3") (pin "P8") (pinfunction "GPIO65_P8") (pintype "bidirectional"))
    )
    (net (code "112") (name "unconnected-(IC3-GPIO66-PadP1)") (class "Default")
      (node (ref "IC3") (pin "P1") (pinfunction "GPIO66_P1") (pintype "bidirectional"))
    )
    (net (code "113") (name "unconnected-(IC3-GPIO67-PadP3)") (class "Default")
      (node (ref "IC3") (pin "P3") (pinfunction "GPIO67_P3") (pintype "bidirectional"))
    )
    (net (code "114") (name "unconnected-(IC3-GPIO68-PadP5)") (class "Default")
      (node (ref "IC3") (pin "P5") (pinfunction "GPIO68_P5") (pintype "bidirectional"))
    )
    (net (code "115") (name "unconnected-(IC3-GPIO69-PadP7)") (class "Default")
      (node (ref "IC3") (pin "P7") (pinfunction "GPIO69_P7") (pintype "bidirectional"))
    )
    (net (code "116") (name "unconnected-(IC3-GPIO114{slash}SPI1_NIRQ-PadP12)") (class "Default")
      (node (ref "IC3") (pin "P12") (pinfunction "GPIO114/SPI1_NIRQ_P12") (pintype "bidirectional"))
    )
    (net (code "117") (name "unconnected-(IC3-GPIO149-PadP49)") (class "Default")
      (node (ref "IC3") (pin "P49") (pinfunction "GPIO149_P49") (pintype "bidirectional"))
    )
    (net (code "118") (name "unconnected-(IC3-GPIO150-PadP50)") (class "Default")
      (node (ref "IC3") (pin "P50") (pinfunction "GPIO150_P50") (pintype "bidirectional"))
    )
    (net (code "119") (name "unconnected-(IC3-GPIO163{slash}CTS3-PadP28)") (class "Default")
      (node (ref "IC3") (pin "P28") (pinfunction "GPIO163/CTS3_P28") (pintype "bidirectional"))
    )
    (net (code "120") (name "unconnected-(IC3-GPIO165{slash}RXD3-PadP29)") (class "Default")
      (node (ref "IC3") (pin "P29") (pinfunction "GPIO165/RXD3_P29") (pintype "bidirectional"))
    )
    (net (code "121") (name "unconnected-(IC3-GPIO166{slash}TXD3-PadP30)") (class "Default")
      (node (ref "IC3") (pin "P30") (pinfunction "GPIO166/TXD3_P30") (pintype "bidirectional"))
    )
    (net (code "122") (name "unconnected-(IC3-GPIO168-PadP2)") (class "Default")
      (node (ref "IC3") (pin "P2") (pinfunction "GPIO168_P2") (pintype "bidirectional"))
    )
    (net (code "123") (name "unconnected-(IC3-GPIO170{slash}1WIRE-PadP27)") (class "Default")
      (node (ref "IC3") (pin "P27") (pinfunction "GPIO170/1WIRE_P27") (pintype "bidirectional"))
    )
    (net (code "124") (name "unconnected-(IC3-GPIO171{slash}SPI1_CLK-PadP11)") (class "Default")
      (node (ref "IC3") (pin "P11") (pinfunction "GPIO171/SPI1_CLK_P11") (pintype "bidirectional"))
    )
    (net (code "125") (name "unconnected-(IC3-GPIO172{slash}SPI1_MOSI-PadP13)") (class "Default")
      (node (ref "IC3") (pin "P13") (pinfunction "GPIO172/SPI1_MOSI_P13") (pintype "bidirectional"))
    )
    (net (code "126") (name "unconnected-(IC3-GPIO173{slash}SPI1_MISO-PadP15)") (class "Default")
      (node (ref "IC3") (pin "P15") (pinfunction "GPIO173/SPI1_MISO_P15") (pintype "bidirectional"))
    )
    (net (code "127") (name "unconnected-(IC3-GPIO174{slash}SPI1_CS0-PadP14)") (class "Default")
      (node (ref "IC3") (pin "P14") (pinfunction "GPIO174/SPI1_CS0_P14") (pintype "bidirectional"))
    )
    (net (code "128") (name "unconnected-(IC3-GPIO175{slash}SPI1_CS1-PadP16)") (class "Default")
      (node (ref "IC3") (pin "P16") (pinfunction "GPIO175/SPI1_CS1_P16") (pintype "bidirectional"))
    )
    (net (code "129") (name "unconnected-(IC3-GPIO176-PadP6)") (class "Default")
      (node (ref "IC3") (pin "P6") (pinfunction "GPIO176_P6") (pintype "bidirectional"))
    )
    (net (code "130") (name "unconnected-(IC3-GPIO186-PadP25)") (class "Default")
      (node (ref "IC3") (pin "P25") (pinfunction "GPIO186_P25") (pintype "bidirectional"))
    )
    (net (code "131") (name "unconnected-(IC3-POWERON-PadP22)") (class "Default")
      (node (ref "IC3") (pin "P22") (pinfunction "POWERON_P22") (pintype "bidirectional"))
    )
    (net (code "132") (name "unconnected-(IC3-PWM0-PadP39)") (class "Default")
      (node (ref "IC3") (pin "P39") (pinfunction "PWM0_P39") (pintype "bidirectional"))
    )
    (net (code "133") (name "unconnected-(IC3-PWM1-PadP40)") (class "Default")
      (node (ref "IC3") (pin "P40") (pinfunction "PWM1_P40") (pintype "bidirectional"))
    )
    (net (code "134") (name "unconnected-(IC3-SYS_EN-PadP19)") (class "Default")
      (node (ref "IC3") (pin "P19") (pinfunction "SYS_EN_P19") (pintype "bidirectional"))
    )
    (net (code "135") (name "unconnected-(IC3-VBACKUP-PadP20)") (class "Default")
      (node (ref "IC3") (pin "P20") (pinfunction "VBACKUP_P20") (pintype "bidirectional"))
    )
    (net (code "136") (name "unconnected-(IC3-VCC_3V3-PadP10)") (class "Default")
      (node (ref "IC3") (pin "P10") (pinfunction "VCC_3V3_P10") (pintype "bidirectional"))
    )
    (net (code "137") (name "unconnected-(U$2-PadP$3)") (class "Default")
      (node (ref "U$2") (pin "P$3") (pinfunction "P$3_P$3") (pintype "bidirectional"))
    )
    (net (code "138") (name "unconnected-(U$11-INVLAID-PadP$10)") (class "Default")
      (node (ref "U$11") (pin "P$10") (pinfunction "INVLAID_P$10") (pintype "output"))
    )
    (net (code "139") (name "unconnected-(U3-(ADC1)PC1-PadP$24)") (class "Default")
      (node (ref "U3") (pin "P$24") (pinfunction "(ADC1)PC1_P$24") (pintype "bidirectional"))
    )
    (net (code "140") (name "unconnected-(U3-(ADC2)PC2-PadP$25)") (class "Default")
      (node (ref "U3") (pin "P$25") (pinfunction "(ADC2)PC2_P$25") (pintype "bidirectional"))
    )
    (net (code "141") (name "unconnected-(U3-(ADC3)PC3-PadP$26)") (class "Default")
      (node (ref "U3") (pin "P$26") (pinfunction "(ADC3)PC3_P$26") (pintype "bidirectional"))
    )
    (net (code "142") (name "unconnected-(U3-(RXD)PD0-PadP$30)") (class "Default")
      (node (ref "U3") (pin "P$30") (pinfunction "(RXD)PD0_P$30") (pintype "bidirectional"))
    )
    (net (code "143") (name "unconnected-(U3-(SS)PB2-PadP$14)") (class "Default")
      (node (ref "U3") (pin "P$14") (pinfunction "(SS)PB2_P$14") (pintype "bidirectional"))
    )
    (net (code "144") (name "unconnected-(U3-(TXD)PD1-PadP$31)") (class "Default")
      (node (ref "U3") (pin "P$31") (pinfunction "(TXD)PD1_P$31") (pintype "bidirectional"))
    )
    (net (code "145") (name "unconnected-(U3-ADC7-PadP$22)") (class "Default")
      (node (ref "U3") (pin "P$22") (pinfunction "ADC7_P$22") (pintype "bidirectional"))
    )
    (net (code "146") (name "unconnected-(U4-FB{slash}NC-PadP$1)") (class "Default")
      (node (ref "U4") (pin "P$1") (pinfunction "FB/NC_P$1") (pintype "bidirectional"))
    )
    (net (code "147") (name "unconnected-(U4-PG-PadP$2)") (class "Default")
      (node (ref "U4") (pin "P$2") (pinfunction "PG_P$2") (pintype "bidirectional"))
    )
  )
)
